# motorBoardSCH.net
KiCad netlist of a schematic drawn in Altium Designer
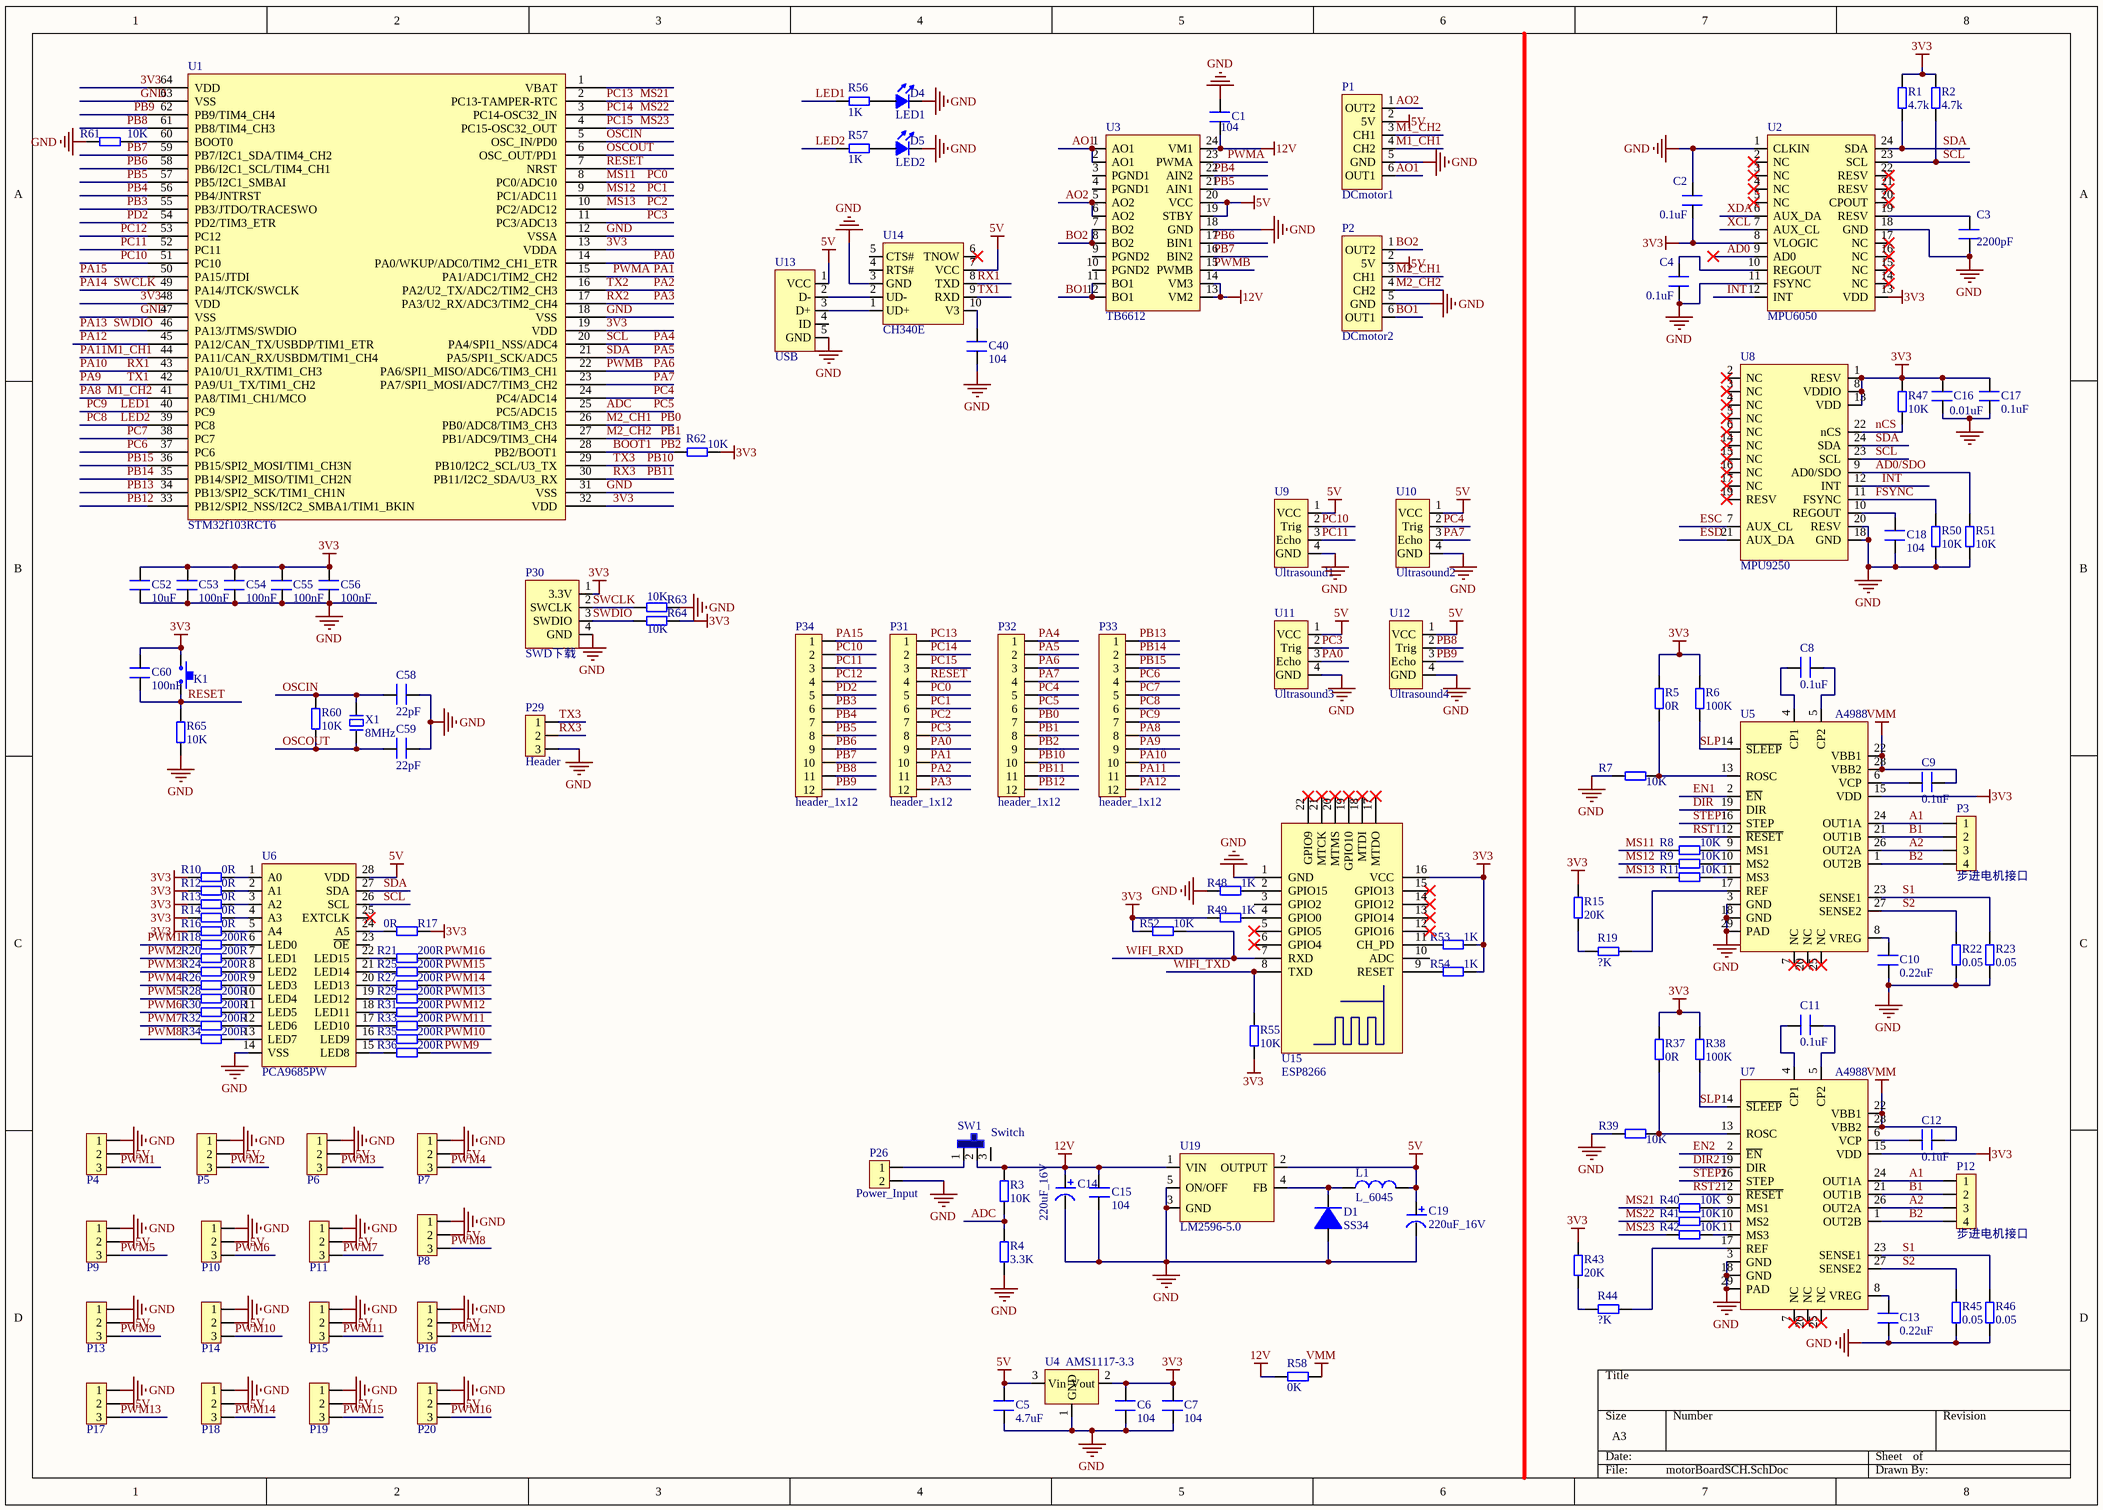
[diagram p0: motorBoardSCH.SchDoc]

(export (version "E")
  (design (tool "Eeschema 10.0.6"))
  (components
    (comp (ref "C1") (value "104") (footprint "C 0603") (libsource (lib "RobotDriverSCHLib") (part "C_0603")))
    (comp (ref "C2")
      (value "0.1uF")
      (footprint "C 0603")
      (libsource (lib "RobotDriverSCHLib") (part "C_0603"))
    )
    (comp (ref "C3")
      (value "2200pF")
      (footprint "C 0603")
      (libsource (lib "RobotDriverSCHLib") (part "C_0603"))
    )
    (comp (ref "C4")
      (value "0.1uF")
      (footprint "C 0603")
      (libsource (lib "RobotDriverSCHLib") (part "C_0603"))
    )
    (comp (ref "C5")
      (value "4.7uF")
      (footprint "C 0603")
      (libsource (lib "RobotDriverSCHLib") (part "C_0603"))
    )
    (comp (ref "C6") (value "104") (footprint "C 0603") (libsource (lib "RobotDriverSCHLib") (part "C_0603")))
    (comp (ref "C7") (value "104") (footprint "C 0603") (libsource (lib "RobotDriverSCHLib") (part "C_0603")))
    (comp (ref "C8")
      (value "0.1uF")
      (footprint "C 0603")
      (libsource (lib "RobotDriverSCHLib") (part "C_0603"))
    )
    (comp (ref "C9")
      (value "0.1uF")
      (footprint "C 0603")
      (libsource (lib "RobotDriverSCHLib") (part "C_0603"))
    )
    (comp (ref "C10")
      (value "0.22uF")
      (footprint "C 0603")
      (libsource (lib "RobotDriverSCHLib") (part "C_0603"))
    )
    (comp (ref "C11")
      (value "0.1uF")
      (footprint "C 0603")
      (libsource (lib "RobotDriverSCHLib") (part "C_0603"))
    )
    (comp (ref "C12")
      (value "0.1uF")
      (footprint "C 0603")
      (libsource (lib "RobotDriverSCHLib") (part "C_0603"))
    )
    (comp (ref "C13")
      (value "0.22uF")
      (footprint "C 0603")
      (libsource (lib "RobotDriverSCHLib") (part "C_0603"))
    )
    (comp (ref "C14")
      (value "220uF_16V")
      (footprint "CM D(6.3*7.7)")
      (libsource (lib "RobotDriverSCHLib") (part "CAP_220uF_16V"))
    )
    (comp (ref "C15")
      (value "104")
      (footprint "C 0603")
      (libsource (lib "RobotDriverSCHLib") (part "C_0603"))
    )
    (comp (ref "C16")
      (value "0.01uF")
      (footprint "C 0603")
      (libsource (lib "RobotDriverSCHLib") (part "C_0603"))
    )
    (comp (ref "C17")
      (value "0.1uF")
      (footprint "C 0603")
      (libsource (lib "RobotDriverSCHLib") (part "C_0603"))
    )
    (comp (ref "C18")
      (value "104")
      (footprint "C 0603")
      (libsource (lib "RobotDriverSCHLib") (part "C_0603"))
    )
    (comp (ref "C19")
      (value "220uF_16V")
      (footprint "CM D(6.3*7.7)")
      (libsource (lib "RobotDriverSCHLib") (part "CAP_220uF_16V"))
    )
    (comp (ref "C40")
      (value "104")
      (footprint "C 0603")
      (libsource (lib "RobotDriverSCHLib") (part "C_0603"))
    )
    (comp (ref "C52")
      (value "10uF")
      (footprint "C 0603")
      (libsource (lib "RobotDriverSCHLib") (part "C_0603"))
    )
    (comp (ref "C53")
      (value "100nF")
      (footprint "C 0603")
      (libsource (lib "RobotDriverSCHLib") (part "C_0603"))
    )
    (comp (ref "C54")
      (value "100nF")
      (footprint "C 0603")
      (libsource (lib "RobotDriverSCHLib") (part "C_0603"))
    )
    (comp (ref "C55")
      (value "100nF")
      (footprint "C 0603")
      (libsource (lib "RobotDriverSCHLib") (part "C_0603"))
    )
    (comp (ref "C56")
      (value "100nF")
      (footprint "C 0603")
      (libsource (lib "RobotDriverSCHLib") (part "C_0603"))
    )
    (comp (ref "C58")
      (value "22pF")
      (footprint "C 0603")
      (libsource (lib "RobotDriverSCHLib") (part "C_0603"))
    )
    (comp (ref "C59")
      (value "22pF")
      (footprint "C 0603")
      (libsource (lib "RobotDriverSCHLib") (part "C_0603"))
    )
    (comp (ref "C60")
      (value "100nF")
      (footprint "C 0603")
      (libsource (lib "RobotDriverSCHLib") (part "C_0603"))
    )
    (comp (ref "D1") (value "SS34") (footprint "SMA") (libsource (lib "RobotDriverSCHLib") (part "SS34")))
    (comp (ref "D4")
      (value "LED1")
      (footprint "LED 0603R")
      (libsource (lib "RobotDriverSCHLib") (part "LED"))
    )
    (comp (ref "D5")
      (value "LED2")
      (footprint "LED 0603R")
      (libsource (lib "RobotDriverSCHLib") (part "LED"))
    )
    (comp (ref "K1")
      (value "key")
      (footprint "TSW SMD-3*6*4.3")
      (libsource (lib "RobotDriverSCHLib") (part "key"))
    )
    (comp (ref "L1")
      (value "L_6045")
      (footprint "NR6045")
      (libsource (lib "RobotDriverSCHLib") (part "L_6045"))
    )
    (comp (ref "P1")
      (value "DCmotor1")
      (footprint "XH2.54-WI-6P")
      (libsource (lib "RobotDriverSCHLib") (part "DCMotor"))
    )
    (comp (ref "P2")
      (value "DCmotor2")
      (footprint "XH2.54-WI-6P")
      (libsource (lib "RobotDriverSCHLib") (part "DCMotor"))
    )
    (comp (ref "P3")
      (value "步进电机接口")
      (footprint "XH2.54-WI-4P")
      (libsource (lib "RobotDriverSCHLib") (part "header_1x4"))
    )
    (comp (ref "P4")
      (value "Head_1x3")
      (footprint "HDR2.54-LI-3P")
      (libsource (lib "RobotDriverSCHLib") (part "Head_1x3"))
    )
    (comp (ref "P5")
      (value "Head_1x3")
      (footprint "HDR2.54-LI-3P")
      (libsource (lib "RobotDriverSCHLib") (part "Head_1x3"))
    )
    (comp (ref "P6")
      (value "Head_1x3")
      (footprint "HDR2.54-LI-3P")
      (libsource (lib "RobotDriverSCHLib") (part "Head_1x3"))
    )
    (comp (ref "P7")
      (value "Head_1x3")
      (footprint "HDR2.54-LI-3P")
      (libsource (lib "RobotDriverSCHLib") (part "Head_1x3"))
    )
    (comp (ref "P8")
      (value "Head_1x3")
      (footprint "HDR2.54-LI-3P")
      (libsource (lib "RobotDriverSCHLib") (part "Head_1x3"))
    )
    (comp (ref "P9")
      (value "Head_1x3")
      (footprint "HDR2.54-LI-3P")
      (libsource (lib "RobotDriverSCHLib") (part "Head_1x3"))
    )
    (comp (ref "P10")
      (value "Head_1x3")
      (footprint "HDR2.54-LI-3P")
      (libsource (lib "RobotDriverSCHLib") (part "Head_1x3"))
    )
    (comp (ref "P11")
      (value "Head_1x3")
      (footprint "HDR2.54-LI-3P")
      (libsource (lib "RobotDriverSCHLib") (part "Head_1x3"))
    )
    (comp (ref "P12")
      (value "步进电机接口")
      (footprint "XH2.54-WI-4P")
      (libsource (lib "RobotDriverSCHLib") (part "header_1x4"))
    )
    (comp (ref "P13")
      (value "Head_1x3")
      (footprint "HDR2.54-LI-3P")
      (libsource (lib "RobotDriverSCHLib") (part "Head_1x3"))
    )
    (comp (ref "P14")
      (value "Head_1x3")
      (footprint "HDR2.54-LI-3P")
      (libsource (lib "RobotDriverSCHLib") (part "Head_1x3"))
    )
    (comp (ref "P15")
      (value "Head_1x3")
      (footprint "HDR2.54-LI-3P")
      (libsource (lib "RobotDriverSCHLib") (part "Head_1x3"))
    )
    (comp (ref "P16")
      (value "Head_1x3")
      (footprint "HDR2.54-LI-3P")
      (libsource (lib "RobotDriverSCHLib") (part "Head_1x3"))
    )
    (comp (ref "P17")
      (value "Head_1x3")
      (footprint "HDR2.54-LI-3P")
      (libsource (lib "RobotDriverSCHLib") (part "Head_1x3"))
    )
    (comp (ref "P18")
      (value "Head_1x3")
      (footprint "HDR2.54-LI-3P")
      (libsource (lib "RobotDriverSCHLib") (part "Head_1x3"))
    )
    (comp (ref "P19")
      (value "Head_1x3")
      (footprint "HDR2.54-LI-3P")
      (libsource (lib "RobotDriverSCHLib") (part "Head_1x3"))
    )
    (comp (ref "P20")
      (value "Head_1x3")
      (footprint "HDR2.54-LI-3P")
      (libsource (lib "RobotDriverSCHLib") (part "Head_1x3"))
    )
    (comp (ref "P26")
      (value "Power_Input")
      (footprint "XH2.54-WI-2P")
      (libsource (lib "RobotDriverSCHLib") (part "header_1x2"))
    )
    (comp (ref "P29")
      (value "Header")
      (footprint "HDR2.54-LI-3P")
      (libsource (lib "RobotDriverSCHLib") (part "header_1x3"))
    )
    (comp (ref "P30")
      (value "SWD下载")
      (footprint "HDR2.54-WI-4P")
      (libsource (lib "RobotDriverSCHLib") (part "SWD"))
    )
    (comp (ref "P31")
      (value "header_1x12")
      (footprint "HDR2.54-LI-12P")
      (libsource (lib "RobotDriverSCHLib") (part "header_1x12"))
    )
    (comp (ref "P32")
      (value "header_1x12")
      (footprint "HDR2.54-LI-12P")
      (libsource (lib "RobotDriverSCHLib") (part "header_1x12"))
    )
    (comp (ref "P33")
      (value "header_1x12")
      (footprint "HDR2.54-LI-12P")
      (libsource (lib "RobotDriverSCHLib") (part "header_1x12"))
    )
    (comp (ref "P34")
      (value "header_1x12")
      (footprint "HDR2.54-LI-12P")
      (libsource (lib "RobotDriverSCHLib") (part "header_1x12"))
    )
    (comp (ref "R1") (value "4.7k") (footprint "0603R") (libsource (lib "RobotDriverSCHLib") (part "R_0603")))
    (comp (ref "R2") (value "4.7k") (footprint "0603R") (libsource (lib "RobotDriverSCHLib") (part "R_0603")))
    (comp (ref "R3") (value "10K") (footprint "0603R") (libsource (lib "RobotDriverSCHLib") (part "R_0603")))
    (comp (ref "R4") (value "3.3K") (footprint "0603R") (libsource (lib "RobotDriverSCHLib") (part "R_0603")))
    (comp (ref "R5") (value "0R") (footprint "0603R") (libsource (lib "RobotDriverSCHLib") (part "R_0603")))
    (comp (ref "R6") (value "100K") (footprint "0603R") (libsource (lib "RobotDriverSCHLib") (part "R_0603")))
    (comp (ref "R7") (value "10K") (footprint "0603R") (libsource (lib "RobotDriverSCHLib") (part "R_0603")))
    (comp (ref "R8") (value "10K") (footprint "0603R") (libsource (lib "RobotDriverSCHLib") (part "R_0603")))
    (comp (ref "R9") (value "10K") (footprint "0603R") (libsource (lib "RobotDriverSCHLib") (part "R_0603")))
    (comp (ref "R10") (value "0R") (footprint "0603R") (libsource (lib "RobotDriverSCHLib") (part "R_0603")))
    (comp (ref "R11") (value "10K") (footprint "0603R") (libsource (lib "RobotDriverSCHLib") (part "R_0603")))
    (comp (ref "R12") (value "0R") (footprint "0603R") (libsource (lib "RobotDriverSCHLib") (part "R_0603")))
    (comp (ref "R13") (value "0R") (footprint "0603R") (libsource (lib "RobotDriverSCHLib") (part "R_0603")))
    (comp (ref "R14") (value "0R") (footprint "0603R") (libsource (lib "RobotDriverSCHLib") (part "R_0603")))
    (comp (ref "R15") (value "20K") (footprint "0603R") (libsource (lib "RobotDriverSCHLib") (part "R_0603")))
    (comp (ref "R16") (value "0R") (footprint "0603R") (libsource (lib "RobotDriverSCHLib") (part "R_0603")))
    (comp (ref "R17") (value "0R") (footprint "0603R") (libsource (lib "RobotDriverSCHLib") (part "R_0603")))
    (comp (ref "R18")
      (value "200R")
      (footprint "0603R")
      (libsource (lib "RobotDriverSCHLib") (part "R_0603"))
    )
    (comp (ref "R19") (value "?K") (footprint "0603R") (libsource (lib "RobotDriverSCHLib") (part "R_0603")))
    (comp (ref "R20")
      (value "200R")
      (footprint "0603R")
      (libsource (lib "RobotDriverSCHLib") (part "R_0603"))
    )
    (comp (ref "R21")
      (value "200R")
      (footprint "0603R")
      (libsource (lib "RobotDriverSCHLib") (part "R_0603"))
    )
    (comp (ref "R22")
      (value "0.05")
      (footprint "0603R")
      (libsource (lib "RobotDriverSCHLib") (part "R_0603"))
    )
    (comp (ref "R23")
      (value "0.05")
      (footprint "0603R")
      (libsource (lib "RobotDriverSCHLib") (part "R_0603"))
    )
    (comp (ref "R24")
      (value "200R")
      (footprint "0603R")
      (libsource (lib "RobotDriverSCHLib") (part "R_0603"))
    )
    (comp (ref "R25")
      (value "200R")
      (footprint "0603R")
      (libsource (lib "RobotDriverSCHLib") (part "R_0603"))
    )
    (comp (ref "R26")
      (value "200R")
      (footprint "0603R")
      (libsource (lib "RobotDriverSCHLib") (part "R_0603"))
    )
    (comp (ref "R27")
      (value "200R")
      (footprint "0603R")
      (libsource (lib "RobotDriverSCHLib") (part "R_0603"))
    )
    (comp (ref "R28")
      (value "200R")
      (footprint "0603R")
      (libsource (lib "RobotDriverSCHLib") (part "R_0603"))
    )
    (comp (ref "R29")
      (value "200R")
      (footprint "0603R")
      (libsource (lib "RobotDriverSCHLib") (part "R_0603"))
    )
    (comp (ref "R30")
      (value "200R")
      (footprint "0603R")
      (libsource (lib "RobotDriverSCHLib") (part "R_0603"))
    )
    (comp (ref "R31")
      (value "200R")
      (footprint "0603R")
      (libsource (lib "RobotDriverSCHLib") (part "R_0603"))
    )
    (comp (ref "R32")
      (value "200R")
      (footprint "0603R")
      (libsource (lib "RobotDriverSCHLib") (part "R_0603"))
    )
    (comp (ref "R33")
      (value "200R")
      (footprint "0603R")
      (libsource (lib "RobotDriverSCHLib") (part "R_0603"))
    )
    (comp (ref "R34")
      (value "200R")
      (footprint "0603R")
      (libsource (lib "RobotDriverSCHLib") (part "R_0603"))
    )
    (comp (ref "R35")
      (value "200R")
      (footprint "0603R")
      (libsource (lib "RobotDriverSCHLib") (part "R_0603"))
    )
    (comp (ref "R36")
      (value "200R")
      (footprint "0603R")
      (libsource (lib "RobotDriverSCHLib") (part "R_0603"))
    )
    (comp (ref "R37") (value "0R") (footprint "0603R") (libsource (lib "RobotDriverSCHLib") (part "R_0603")))
    (comp (ref "R38")
      (value "100K")
      (footprint "0603R")
      (libsource (lib "RobotDriverSCHLib") (part "R_0603"))
    )
    (comp (ref "R39") (value "10K") (footprint "0603R") (libsource (lib "RobotDriverSCHLib") (part "R_0603")))
    (comp (ref "R40") (value "10K") (footprint "0603R") (libsource (lib "RobotDriverSCHLib") (part "R_0603")))
    (comp (ref "R41") (value "10K") (footprint "0603R") (libsource (lib "RobotDriverSCHLib") (part "R_0603")))
    (comp (ref "R42") (value "10K") (footprint "0603R") (libsource (lib "RobotDriverSCHLib") (part "R_0603")))
    (comp (ref "R43") (value "20K") (footprint "0603R") (libsource (lib "RobotDriverSCHLib") (part "R_0603")))
    (comp (ref "R44") (value "?K") (footprint "0603R") (libsource (lib "RobotDriverSCHLib") (part "R_0603")))
    (comp (ref "R45")
      (value "0.05")
      (footprint "0603R")
      (libsource (lib "RobotDriverSCHLib") (part "R_0603"))
    )
    (comp (ref "R46")
      (value "0.05")
      (footprint "0603R")
      (libsource (lib "RobotDriverSCHLib") (part "R_0603"))
    )
    (comp (ref "R47") (value "10K") (footprint "0603R") (libsource (lib "RobotDriverSCHLib") (part "R_0603")))
    (comp (ref "R48") (value "1K") (footprint "0603R") (libsource (lib "RobotDriverSCHLib") (part "R_0603")))
    (comp (ref "R49") (value "1K") (footprint "0603R") (libsource (lib "RobotDriverSCHLib") (part "R_0603")))
    (comp (ref "R50") (value "10K") (footprint "0603R") (libsource (lib "RobotDriverSCHLib") (part "R_0603")))
    (comp (ref "R51") (value "10K") (footprint "0603R") (libsource (lib "RobotDriverSCHLib") (part "R_0603")))
    (comp (ref "R52") (value "10K") (footprint "0603R") (libsource (lib "RobotDriverSCHLib") (part "R_0603")))
    (comp (ref "R53") (value "1K") (footprint "0603R") (libsource (lib "RobotDriverSCHLib") (part "R_0603")))
    (comp (ref "R54") (value "1K") (footprint "0603R") (libsource (lib "RobotDriverSCHLib") (part "R_0603")))
    (comp (ref "R55") (value "10K") (footprint "0603R") (libsource (lib "RobotDriverSCHLib") (part "R_0603")))
    (comp (ref "R56") (value "1K") (footprint "0603R") (libsource (lib "RobotDriverSCHLib") (part "R_0603")))
    (comp (ref "R57") (value "1K") (footprint "0603R") (libsource (lib "RobotDriverSCHLib") (part "R_0603")))
    (comp (ref "R58") (value "0K") (footprint "0603R") (libsource (lib "RobotDriverSCHLib") (part "R_0603")))
    (comp (ref "R60") (value "10K") (footprint "0603R") (libsource (lib "RobotDriverSCHLib") (part "R_0603")))
    (comp (ref "R61") (value "10K") (footprint "0603R") (libsource (lib "RobotDriverSCHLib") (part "R_0603")))
    (comp (ref "R62") (value "10K") (footprint "0603R") (libsource (lib "RobotDriverSCHLib") (part "R_0603")))
    (comp (ref "R63") (value "10K") (footprint "0603R") (libsource (lib "RobotDriverSCHLib") (part "R_0603")))
    (comp (ref "R64") (value "10K") (footprint "0603R") (libsource (lib "RobotDriverSCHLib") (part "R_0603")))
    (comp (ref "R65") (value "10K") (footprint "0603R") (libsource (lib "RobotDriverSCHLib") (part "R_0603")))
    (comp (ref "SW1")
      (value "Switch")
      (footprint "SS12D10")
      (libsource (lib "RobotDriverSCHLib") (part "SS12D10"))
    )
    (comp (ref "U1")
      (value "STM32f103RCT6")
      (footprint "LQFP_64")
      (libsource (lib "RobotDriverSCHLib") (part "STM32f103RCT6"))
    )
    (comp (ref "U2")
      (value "MPU6050")
      (footprint "QFN24 4x4")
      (libsource (lib "RobotDriverSCHLib") (part "MPU6050"))
    )
    (comp (ref "U3")
      (value "TB6612")
      (footprint "SSOP24")
      (libsource (lib "RobotDriverSCHLib") (part "TB6612FNG"))
    )
    (comp (ref "U4")
      (value "AMS1117-3.3")
      (footprint "SOT-223")
      (libsource (lib "RobotDriverSCHLib") (part "AMS1117-3.3"))
    )
    (comp (ref "U5")
      (value "A4988")
      (footprint "QFN28 5x5")
      (libsource (lib "RobotDriverSCHLib") (part "A4988"))
    )
    (comp (ref "U6")
      (value "PCA9685PW")
      (footprint "TSSOP28")
      (libsource (lib "RobotDriverSCHLib") (part "PCA9685PW"))
    )
    (comp (ref "U7")
      (value "A4988")
      (footprint "QFN28 5x5")
      (libsource (lib "RobotDriverSCHLib") (part "A4988"))
    )
    (comp (ref "U8")
      (value "MPU9250")
      (footprint "QFN24_3x3")
      (libsource (lib "RobotDriverSCHLib") (part "MPU9250"))
    )
    (comp (ref "U9")
      (value "Ultrasound1")
      (footprint "超声波模块")
      (libsource (lib "RobotDriverSCHLib") (part "Ultrasound"))
    )
    (comp (ref "U10")
      (value "Ultrasound2")
      (footprint "超声波模块")
      (libsource (lib "RobotDriverSCHLib") (part "Ultrasound"))
    )
    (comp (ref "U11")
      (value "Ultrasound3")
      (footprint "超声波模块")
      (libsource (lib "RobotDriverSCHLib") (part "Ultrasound"))
    )
    (comp (ref "U12")
      (value "Ultrasound4")
      (footprint "超声波模块")
      (libsource (lib "RobotDriverSCHLib") (part "Ultrasound"))
    )
    (comp (ref "U13") (value "USB") (footprint "USB-MICRO_D") (libsource (lib "pin_pi") (part "MicroUSB_D")))
    (comp (ref "U14") (value "CH340E") (footprint "CH340E") (libsource (lib "pin_pi") (part "CH340E")))
    (comp (ref "U15")
      (value "ESP8266")
      (footprint "ESP8266")
      (libsource (lib "RobotDriverSCHLib") (part "ESP8266"))
    )
    (comp (ref "U19")
      (value "LM2596-5.0")
      (footprint "TO263-5A")
      (libsource (lib "RobotDriverSCHLib") (part "LM2596-5.0"))
    )
    (comp (ref "X1")
      (value "8MHz")
      (footprint "OSC HC-49SMD")
      (libsource (lib "RobotDriverSCHLib") (part "XTAL_8MHz"))
    )
  )
  (nets
    (net (code "1") (name "/A1") (class "Default")
      (node (ref "P12") (pin "1") (pinfunction "1_1") (pintype "passive"))
      (node (ref "P3") (pin "1") (pinfunction "1_1") (pintype "passive"))
      (node (ref "U5") (pin "24") (pinfunction "OUT1A_24") (pintype "passive"))
      (node (ref "U7") (pin "24") (pinfunction "OUT1A_24") (pintype "passive"))
    )
    (net (code "2") (name "/A2") (class "Default")
      (node (ref "P12") (pin "3") (pinfunction "3_3") (pintype "passive"))
      (node (ref "P3") (pin "3") (pinfunction "3_3") (pintype "passive"))
      (node (ref "U5") (pin "26") (pinfunction "OUT2A_26") (pintype "passive"))
      (node (ref "U7") (pin "26") (pinfunction "OUT2A_26") (pintype "passive"))
    )
    (net (code "3") (name "/AD0") (class "Default")
      (node (ref "U2") (pin "9") (pinfunction "AD0_9") (pintype "passive+no_connect"))
    )
    (net (code "4") (name "/AD0{slash}SDO") (class "Default")
      (node (ref "R51") (pin "2") (pinfunction "2_2") (pintype "passive"))
      (node (ref "U8") (pin "9") (pinfunction "AD0/SDO_9") (pintype "passive"))
    )
    (net (code "5") (name "/ADC") (class "Default")
      (node (ref "P32") (pin "6") (pinfunction "6_6") (pintype "passive"))
      (node (ref "R3") (pin "1") (pinfunction "1_1") (pintype "passive"))
      (node (ref "R4") (pin "2") (pinfunction "2_2") (pintype "passive"))
      (node (ref "U1") (pin "25") (pinfunction "PC5/ADC15_25") (pintype "passive"))
    )
    (net (code "6") (name "/AO1") (class "Default")
      (node (ref "P1") (pin "6") (pinfunction "OUT1_6") (pintype "passive"))
      (node (ref "U3") (pin "1") (pinfunction "AO1_1") (pintype "passive"))
      (node (ref "U3") (pin "2") (pinfunction "AO1_2") (pintype "passive"))
    )
    (net (code "7") (name "/AO2") (class "Default")
      (node (ref "P1") (pin "1") (pinfunction "OUT2_1") (pintype "passive"))
      (node (ref "U3") (pin "5") (pinfunction "AO2_5") (pintype "passive"))
      (node (ref "U3") (pin "6") (pinfunction "AO2_6") (pintype "passive"))
    )
    (net (code "8") (name "/B1") (class "Default")
      (node (ref "P12") (pin "2") (pinfunction "2_2") (pintype "passive"))
      (node (ref "P3") (pin "2") (pinfunction "2_2") (pintype "passive"))
      (node (ref "U5") (pin "21") (pinfunction "OUT1B_21") (pintype "passive"))
      (node (ref "U7") (pin "21") (pinfunction "OUT1B_21") (pintype "passive"))
    )
    (net (code "9") (name "/B2") (class "Default")
      (node (ref "P12") (pin "4") (pinfunction "4_4") (pintype "passive"))
      (node (ref "P3") (pin "4") (pinfunction "4_4") (pintype "passive"))
      (node (ref "U5") (pin "1") (pinfunction "OUT2B_1") (pintype "passive"))
      (node (ref "U7") (pin "1") (pinfunction "OUT2B_1") (pintype "passive"))
    )
    (net (code "10") (name "/BO1") (class "Default")
      (node (ref "P2") (pin "6") (pinfunction "OUT1_6") (pintype "passive"))
      (node (ref "U3") (pin "11") (pinfunction "BO1_11") (pintype "passive"))
      (node (ref "U3") (pin "12") (pinfunction "BO1_12") (pintype "passive"))
    )
    (net (code "11") (name "/BO2") (class "Default")
      (node (ref "P2") (pin "1") (pinfunction "OUT2_1") (pintype "passive"))
      (node (ref "U3") (pin "7") (pinfunction "BO2_7") (pintype "passive"))
      (node (ref "U3") (pin "8") (pinfunction "BO2_8") (pintype "passive"))
    )
    (net (code "12") (name "/BOOT1") (class "Default")
      (node (ref "P32") (pin "9") (pinfunction "9_9") (pintype "passive"))
      (node (ref "R62") (pin "2") (pinfunction "2_2") (pintype "passive"))
      (node (ref "U1") (pin "28") (pinfunction "PB2/BOOT1_28") (pintype "passive"))
    )
    (net (code "13") (name "/DIR") (class "Default")
      (node (ref "U5") (pin "19") (pinfunction "DIR_19") (pintype "passive"))
    )
    (net (code "14") (name "/DIR2") (class "Default")
      (node (ref "U7") (pin "19") (pinfunction "DIR_19") (pintype "passive"))
    )
    (net (code "15") (name "/EN1") (class "Default")
      (node (ref "U5") (pin "2") (pinfunction "~{EN}_2") (pintype "passive"))
    )
    (net (code "16") (name "/EN2") (class "Default")
      (node (ref "U7") (pin "2") (pinfunction "~{EN}_2") (pintype "passive"))
    )
    (net (code "17") (name "/ESC") (class "Default")
      (node (ref "U8") (pin "7") (pinfunction "AUX_CL_7") (pintype "passive"))
    )
    (net (code "18") (name "/ESD") (class "Default")
      (node (ref "U8") (pin "21") (pinfunction "AUX_DA_21") (pintype "passive"))
    )
    (net (code "19") (name "/FSYNC") (class "Default")
      (node (ref "R50") (pin "2") (pinfunction "2_2") (pintype "passive"))
      (node (ref "U8") (pin "11") (pinfunction "FSYNC_11") (pintype "passive"))
    )
    (net (code "20") (name "/INT") (class "Default")
      (node (ref "U2") (pin "12") (pinfunction "INT_12") (pintype "passive"))
      (node (ref "U8") (pin "12") (pinfunction "INT_12") (pintype "passive"))
    )
    (net (code "21") (name "/LED1") (class "Default")
      (node (ref "P33") (pin "7") (pinfunction "7_7") (pintype "passive"))
      (node (ref "R56") (pin "1") (pinfunction "1_1") (pintype "passive"))
      (node (ref "U1") (pin "40") (pinfunction "PC9_40") (pintype "passive"))
    )
    (net (code "22") (name "/LED2") (class "Default")
      (node (ref "P33") (pin "6") (pinfunction "6_6") (pintype "passive"))
      (node (ref "R57") (pin "1") (pinfunction "1_1") (pintype "passive"))
      (node (ref "U1") (pin "39") (pinfunction "PC8_39") (pintype "passive"))
    )
    (net (code "23") (name "/M1_CH1") (class "Default")
      (node (ref "P1") (pin "4") (pinfunction "CH2_4") (pintype "passive"))
      (node (ref "P33") (pin "11") (pinfunction "11_11") (pintype "passive"))
      (node (ref "U1") (pin "44") (pinfunction "PA11/CAN_RX/USBDM/TIM1_CH4_44") (pintype "passive"))
    )
    (net (code "24") (name "/M1_CH2") (class "Default")
      (node (ref "P1") (pin "3") (pinfunction "CH1_3") (pintype "passive"))
      (node (ref "P33") (pin "8") (pinfunction "8_8") (pintype "passive"))
      (node (ref "U1") (pin "41") (pinfunction "PA8/TIM1_CH1/MCO_41") (pintype "passive"))
    )
    (net (code "25") (name "/M2_CH1") (class "Default")
      (node (ref "P2") (pin "3") (pinfunction "CH1_3") (pintype "passive"))
      (node (ref "P32") (pin "7") (pinfunction "7_7") (pintype "passive"))
      (node (ref "U1") (pin "26") (pinfunction "PB0/ADC8/TIM3_CH3_26") (pintype "passive"))
    )
    (net (code "26") (name "/M2_CH2") (class "Default")
      (node (ref "P2") (pin "4") (pinfunction "CH2_4") (pintype "passive"))
      (node (ref "P32") (pin "8") (pinfunction "8_8") (pintype "passive"))
      (node (ref "U1") (pin "27") (pinfunction "PB1/ADC9/TIM3_CH4_27") (pintype "passive"))
    )
    (net (code "27") (name "/MS11") (class "Default")
      (node (ref "P31") (pin "5") (pinfunction "5_5") (pintype "passive"))
      (node (ref "R8") (pin "2") (pinfunction "2_2") (pintype "passive"))
      (node (ref "U1") (pin "8") (pinfunction "PC0/ADC10_8") (pintype "passive"))
    )
    (net (code "28") (name "/MS12") (class "Default")
      (node (ref "P31") (pin "6") (pinfunction "6_6") (pintype "passive"))
      (node (ref "R9") (pin "2") (pinfunction "2_2") (pintype "passive"))
      (node (ref "U1") (pin "9") (pinfunction "PC1/ADC11_9") (pintype "passive"))
    )
    (net (code "29") (name "/MS13") (class "Default")
      (node (ref "P31") (pin "7") (pinfunction "7_7") (pintype "passive"))
      (node (ref "R11") (pin "2") (pinfunction "2_2") (pintype "passive"))
      (node (ref "U1") (pin "10") (pinfunction "PC2/ADC12_10") (pintype "passive"))
    )
    (net (code "30") (name "/MS21") (class "Default")
      (node (ref "P31") (pin "1") (pinfunction "1_1") (pintype "passive"))
      (node (ref "R40") (pin "2") (pinfunction "2_2") (pintype "passive"))
      (node (ref "U1") (pin "2") (pinfunction "PC13-TAMPER-RTC_2") (pintype "passive"))
    )
    (net (code "31") (name "/MS22") (class "Default")
      (node (ref "P31") (pin "2") (pinfunction "2_2") (pintype "passive"))
      (node (ref "R41") (pin "2") (pinfunction "2_2") (pintype "passive"))
      (node (ref "U1") (pin "3") (pinfunction "PC14-OSC32_IN_3") (pintype "passive"))
    )
    (net (code "32") (name "/MS23") (class "Default")
      (node (ref "P31") (pin "3") (pinfunction "3_3") (pintype "passive"))
      (node (ref "R42") (pin "2") (pinfunction "2_2") (pintype "passive"))
      (node (ref "U1") (pin "4") (pinfunction "PC15-OSC32_OUT_4") (pintype "passive"))
    )
    (net (code "33") (name "/OSCIN") (class "Default")
      (node (ref "C58") (pin "2") (pinfunction "2_2") (pintype "passive"))
      (node (ref "R60") (pin "2") (pinfunction "2_2") (pintype "passive"))
      (node (ref "U1") (pin "5") (pinfunction "OSC_IN/PD0_5") (pintype "passive"))
      (node (ref "X1") (pin "2") (pinfunction "2_2") (pintype "passive"))
    )
    (net (code "34") (name "/OSCOUT") (class "Default")
      (node (ref "C59") (pin "2") (pinfunction "2_2") (pintype "passive"))
      (node (ref "R60") (pin "1") (pinfunction "1_1") (pintype "passive"))
      (node (ref "U1") (pin "6") (pinfunction "OSC_OUT/PD1_6") (pintype "passive"))
      (node (ref "X1") (pin "1") (pinfunction "1_1") (pintype "passive"))
    )
    (net (code "35") (name "/PA0") (class "Default")
      (node (ref "P31") (pin "9") (pinfunction "9_9") (pintype "passive"))
      (node (ref "U1") (pin "14") (pinfunction "PA0/WKUP/ADC0/TIM2_CH1_ETR_14") (pintype "passive"))
      (node (ref "U11") (pin "3") (pinfunction "Echo_3") (pintype "passive"))
    )
    (net (code "36") (name "/PA1") (class "Default")
      (node (ref "P31") (pin "10") (pinfunction "10_10") (pintype "passive"))
      (node (ref "U1") (pin "15") (pinfunction "PA1/ADC1/TIM2_CH2_15") (pintype "passive"))
      (node (ref "U3") (pin "23") (pinfunction "PWMA_23") (pintype "passive"))
    )
    (net (code "37") (name "/PA2") (class "Default")
      (node (ref "P31") (pin "11") (pinfunction "11_11") (pintype "passive"))
      (node (ref "U1") (pin "16") (pinfunction "PA2/U2_TX/ADC2/TIM2_CH3_16") (pintype "passive"))
    )
    (net (code "38") (name "/PA3") (class "Default")
      (node (ref "P31") (pin "12") (pinfunction "12_12") (pintype "passive"))
      (node (ref "U1") (pin "17") (pinfunction "PA3/U2_RX/ADC3/TIM2_CH4_17") (pintype "passive"))
    )
    (net (code "39") (name "/PA4") (class "Default")
      (node (ref "P32") (pin "1") (pinfunction "1_1") (pintype "passive"))
      (node (ref "R2") (pin "1") (pinfunction "1_1") (pintype "passive"))
      (node (ref "U1") (pin "20") (pinfunction "PA4/SPI1_NSS/ADC4_20") (pintype "passive"))
      (node (ref "U2") (pin "23") (pinfunction "SCL_23") (pintype "passive"))
      (node (ref "U6") (pin "26") (pinfunction "SCL_26") (pintype "passive"))
      (node (ref "U8") (pin "23") (pinfunction "SCL_23") (pintype "passive"))
    )
    (net (code "40") (name "/PA5") (class "Default")
      (node (ref "P32") (pin "2") (pinfunction "2_2") (pintype "passive"))
      (node (ref "R1") (pin "1") (pinfunction "1_1") (pintype "passive"))
      (node (ref "U1") (pin "21") (pinfunction "PA5/SPI1_SCK/ADC5_21") (pintype "passive"))
      (node (ref "U2") (pin "24") (pinfunction "SDA_24") (pintype "passive"))
      (node (ref "U6") (pin "27") (pinfunction "SDA_27") (pintype "passive"))
      (node (ref "U8") (pin "24") (pinfunction "SDA_24") (pintype "passive"))
    )
    (net (code "41") (name "/PA6") (class "Default")
      (node (ref "P32") (pin "3") (pinfunction "3_3") (pintype "passive"))
      (node (ref "U1") (pin "22") (pinfunction "PA6/SPI1_MISO/ADC6/TIM3_CH1_22") (pintype "passive"))
      (node (ref "U3") (pin "15") (pinfunction "PWMB_15") (pintype "passive"))
    )
    (net (code "42") (name "/PA7") (class "Default")
      (node (ref "P32") (pin "4") (pinfunction "4_4") (pintype "passive"))
      (node (ref "U1") (pin "23") (pinfunction "PA7/SPI1_MOSI/ADC7/TIM3_CH2_23") (pintype "passive"))
      (node (ref "U10") (pin "3") (pinfunction "Echo_3") (pintype "passive"))
    )
    (net (code "43") (name "/PA9") (class "Default")
      (node (ref "P33") (pin "9") (pinfunction "9_9") (pintype "passive"))
      (node (ref "U1") (pin "42") (pinfunction "PA9/U1_TX/TIM1_CH2_42") (pintype "passive"))
      (node (ref "U14") (pin "9") (pinfunction "RXD_9") (pintype "passive"))
    )
    (net (code "44") (name "/PA10") (class "Default")
      (node (ref "P33") (pin "10") (pinfunction "10_10") (pintype "passive"))
      (node (ref "U1") (pin "43") (pinfunction "PA10/U1_RX/TIM1_CH3_43") (pintype "passive"))
      (node (ref "U14") (pin "8") (pinfunction "TXD_8") (pintype "passive"))
    )
    (net (code "45") (name "/PA12") (class "Default")
      (node (ref "P33") (pin "12") (pinfunction "12_12") (pintype "passive"))
      (node (ref "U1") (pin "45") (pinfunction "PA12/CAN_TX/USBDP/TIM1_ETR_45") (pintype "passive"))
    )
    (net (code "46") (name "/PA13") (class "Default")
      (node (ref "P30") (pin "3") (pinfunction "SWDIO_3") (pintype "passive"))
      (node (ref "R64") (pin "2") (pinfunction "2_2") (pintype "passive"))
      (node (ref "U1") (pin "46") (pinfunction "PA13/JTMS/SWDIO_46") (pintype "passive"))
    )
    (net (code "47") (name "/PA14") (class "Default")
      (node (ref "P30") (pin "2") (pinfunction "SWCLK_2") (pintype "passive"))
      (node (ref "R63") (pin "2") (pinfunction "2_2") (pintype "passive"))
      (node (ref "U1") (pin "49") (pinfunction "PA14/JTCK/SWCLK_49") (pintype "passive"))
    )
    (net (code "48") (name "/PA15") (class "Default")
      (node (ref "P34") (pin "1") (pinfunction "1_1") (pintype "passive"))
      (node (ref "U1") (pin "50") (pinfunction "PA15/JTDI_50") (pintype "passive"))
    )
    (net (code "49") (name "/PB3") (class "Default")
      (node (ref "P34") (pin "6") (pinfunction "6_6") (pintype "passive"))
      (node (ref "U1") (pin "55") (pinfunction "PB3/JTDO/TRACESWO_55") (pintype "passive"))
    )
    (net (code "50") (name "/PB4") (class "Default")
      (node (ref "P34") (pin "7") (pinfunction "7_7") (pintype "passive"))
      (node (ref "U1") (pin "56") (pinfunction "PB4/JNTRST_56") (pintype "passive"))
      (node (ref "U3") (pin "22") (pinfunction "AIN2_22") (pintype "passive"))
    )
    (net (code "51") (name "/PB5") (class "Default")
      (node (ref "P34") (pin "8") (pinfunction "8_8") (pintype "passive"))
      (node (ref "U1") (pin "57") (pinfunction "PB5/I2C1_SMBAI_57") (pintype "passive"))
      (node (ref "U3") (pin "21") (pinfunction "AIN1_21") (pintype "passive"))
    )
    (net (code "52") (name "/PB6") (class "Default")
      (node (ref "P34") (pin "9") (pinfunction "9_9") (pintype "passive"))
      (node (ref "U1") (pin "58") (pinfunction "PB6/I2C1_SCL/TIM4_CH1_58") (pintype "passive"))
      (node (ref "U3") (pin "17") (pinfunction "BIN1_17") (pintype "passive"))
    )
    (net (code "53") (name "/PB7") (class "Default")
      (node (ref "P34") (pin "10") (pinfunction "10_10") (pintype "passive"))
      (node (ref "U1") (pin "59") (pinfunction "PB7/I2C1_SDA/TIM4_CH2_59") (pintype "passive"))
      (node (ref "U3") (pin "16") (pinfunction "BIN2_16") (pintype "passive"))
    )
    (net (code "54") (name "/PB8") (class "Default")
      (node (ref "P34") (pin "11") (pinfunction "11_11") (pintype "passive"))
      (node (ref "U1") (pin "61") (pinfunction "PB8/TIM4_CH3_61") (pintype "passive"))
      (node (ref "U12") (pin "2") (pinfunction "Trig_2") (pintype "passive"))
    )
    (net (code "55") (name "/PB9") (class "Default")
      (node (ref "P34") (pin "12") (pinfunction "12_12") (pintype "passive"))
      (node (ref "U1") (pin "62") (pinfunction "PB9/TIM4_CH4_62") (pintype "passive"))
      (node (ref "U12") (pin "3") (pinfunction "Echo_3") (pintype "passive"))
    )
    (net (code "56") (name "/PB10") (class "Default")
      (node (ref "P29") (pin "1") (pinfunction "1_1") (pintype "passive"))
      (node (ref "P32") (pin "10") (pinfunction "10_10") (pintype "passive"))
      (node (ref "U1") (pin "29") (pinfunction "PB10/I2C2_SCL/U3_TX_29") (pintype "passive"))
    )
    (net (code "57") (name "/PB11") (class "Default")
      (node (ref "P29") (pin "2") (pinfunction "2_2") (pintype "passive"))
      (node (ref "P32") (pin "11") (pinfunction "11_11") (pintype "passive"))
      (node (ref "U1") (pin "30") (pinfunction "PB11/I2C2_SDA/U3_RX_30") (pintype "passive"))
    )
    (net (code "58") (name "/PB12") (class "Default")
      (node (ref "P32") (pin "12") (pinfunction "12_12") (pintype "passive"))
      (node (ref "U1") (pin "33") (pinfunction "PB12/SPI2_NSS/I2C2_SMBA1/TIM1_BKIN_33") (pintype "passive"))
    )
    (net (code "59") (name "/PB13") (class "Default")
      (node (ref "P33") (pin "1") (pinfunction "1_1") (pintype "passive"))
      (node (ref "U1") (pin "34") (pinfunction "PB13/SPI2_SCK/TIM1_CH1N_34") (pintype "passive"))
    )
    (net (code "60") (name "/PB14") (class "Default")
      (node (ref "P33") (pin "2") (pinfunction "2_2") (pintype "passive"))
      (node (ref "U1") (pin "35") (pinfunction "PB14/SPI2_MISO/TIM1_CH2N_35") (pintype "passive"))
    )
    (net (code "61") (name "/PB15") (class "Default")
      (node (ref "P33") (pin "3") (pinfunction "3_3") (pintype "passive"))
      (node (ref "U1") (pin "36") (pinfunction "PB15/SPI2_MOSI/TIM1_CH3N_36") (pintype "passive"))
    )
    (net (code "62") (name "/PC3") (class "Default")
      (node (ref "P31") (pin "8") (pinfunction "8_8") (pintype "passive"))
      (node (ref "U1") (pin "11") (pinfunction "PC3/ADC13_11") (pintype "passive"))
      (node (ref "U11") (pin "2") (pinfunction "Trig_2") (pintype "passive"))
    )
    (net (code "63") (name "/PC4") (class "Default")
      (node (ref "P32") (pin "5") (pinfunction "5_5") (pintype "passive"))
      (node (ref "U1") (pin "24") (pinfunction "PC4/ADC14_24") (pintype "passive"))
      (node (ref "U10") (pin "2") (pinfunction "Trig_2") (pintype "passive"))
    )
    (net (code "64") (name "/PC6") (class "Default")
      (node (ref "P33") (pin "4") (pinfunction "4_4") (pintype "passive"))
      (node (ref "U1") (pin "37") (pinfunction "PC6_37") (pintype "passive"))
    )
    (net (code "65") (name "/PC7") (class "Default")
      (node (ref "P33") (pin "5") (pinfunction "5_5") (pintype "passive"))
      (node (ref "U1") (pin "38") (pinfunction "PC7_38") (pintype "passive"))
    )
    (net (code "66") (name "/PC10") (class "Default")
      (node (ref "P34") (pin "2") (pinfunction "2_2") (pintype "passive"))
      (node (ref "U1") (pin "51") (pinfunction "PC10_51") (pintype "passive"))
      (node (ref "U9") (pin "2") (pinfunction "Trig_2") (pintype "passive"))
    )
    (net (code "67") (name "/PC11") (class "Default")
      (node (ref "P34") (pin "3") (pinfunction "3_3") (pintype "passive"))
      (node (ref "U1") (pin "52") (pinfunction "PC11_52") (pintype "passive"))
      (node (ref "U9") (pin "3") (pinfunction "Echo_3") (pintype "passive"))
    )
    (net (code "68") (name "/PC12") (class "Default")
      (node (ref "P34") (pin "4") (pinfunction "4_4") (pintype "passive"))
      (node (ref "U1") (pin "53") (pinfunction "PC12_53") (pintype "passive"))
    )
    (net (code "69") (name "/PD2") (class "Default")
      (node (ref "P34") (pin "5") (pinfunction "5_5") (pintype "passive"))
      (node (ref "U1") (pin "54") (pinfunction "PD2/TIM3_ETR_54") (pintype "passive"))
    )
    (net (code "70") (name "/PWM1") (class "Default")
      (node (ref "P4") (pin "3") (pinfunction "3_3") (pintype "passive"))
      (node (ref "R18") (pin "1") (pinfunction "1_1") (pintype "passive"))
    )
    (net (code "71") (name "/PWM2") (class "Default")
      (node (ref "P5") (pin "3") (pinfunction "3_3") (pintype "passive"))
      (node (ref "R20") (pin "1") (pinfunction "1_1") (pintype "passive"))
    )
    (net (code "72") (name "/PWM3") (class "Default")
      (node (ref "P6") (pin "3") (pinfunction "3_3") (pintype "passive"))
      (node (ref "R24") (pin "1") (pinfunction "1_1") (pintype "passive"))
    )
    (net (code "73") (name "/PWM4") (class "Default")
      (node (ref "P7") (pin "3") (pinfunction "3_3") (pintype "passive"))
      (node (ref "R26") (pin "1") (pinfunction "1_1") (pintype "passive"))
    )
    (net (code "74") (name "/PWM5") (class "Default")
      (node (ref "P9") (pin "3") (pinfunction "3_3") (pintype "passive"))
      (node (ref "R28") (pin "1") (pinfunction "1_1") (pintype "passive"))
    )
    (net (code "75") (name "/PWM6") (class "Default")
      (node (ref "P10") (pin "3") (pinfunction "3_3") (pintype "passive"))
      (node (ref "R30") (pin "1") (pinfunction "1_1") (pintype "passive"))
    )
    (net (code "76") (name "/PWM7") (class "Default")
      (node (ref "P11") (pin "3") (pinfunction "3_3") (pintype "passive"))
      (node (ref "R32") (pin "1") (pinfunction "1_1") (pintype "passive"))
    )
    (net (code "77") (name "/PWM8") (class "Default")
      (node (ref "P8") (pin "3") (pinfunction "3_3") (pintype "passive"))
      (node (ref "R34") (pin "1") (pinfunction "1_1") (pintype "passive"))
    )
    (net (code "78") (name "/PWM9") (class "Default")
      (node (ref "P13") (pin "3") (pinfunction "3_3") (pintype "passive"))
      (node (ref "R36") (pin "1") (pinfunction "1_1") (pintype "passive"))
    )
    (net (code "79") (name "/PWM10") (class "Default")
      (node (ref "P14") (pin "3") (pinfunction "3_3") (pintype "passive"))
      (node (ref "R35") (pin "1") (pinfunction "1_1") (pintype "passive"))
    )
    (net (code "80") (name "/PWM11") (class "Default")
      (node (ref "P15") (pin "3") (pinfunction "3_3") (pintype "passive"))
      (node (ref "R33") (pin "1") (pinfunction "1_1") (pintype "passive"))
    )
    (net (code "81") (name "/PWM12") (class "Default")
      (node (ref "P16") (pin "3") (pinfunction "3_3") (pintype "passive"))
      (node (ref "R31") (pin "1") (pinfunction "1_1") (pintype "passive"))
    )
    (net (code "82") (name "/PWM13") (class "Default")
      (node (ref "P17") (pin "3") (pinfunction "3_3") (pintype "passive"))
      (node (ref "R29") (pin "1") (pinfunction "1_1") (pintype "passive"))
    )
    (net (code "83") (name "/PWM14") (class "Default")
      (node (ref "P18") (pin "3") (pinfunction "3_3") (pintype "passive"))
      (node (ref "R27") (pin "1") (pinfunction "1_1") (pintype "passive"))
    )
    (net (code "84") (name "/PWM15") (class "Default")
      (node (ref "P19") (pin "3") (pinfunction "3_3") (pintype "passive"))
      (node (ref "R25") (pin "1") (pinfunction "1_1") (pintype "passive"))
    )
    (net (code "85") (name "/PWM16") (class "Default")
      (node (ref "P20") (pin "3") (pinfunction "3_3") (pintype "passive"))
      (node (ref "R21") (pin "1") (pinfunction "1_1") (pintype "passive"))
    )
    (net (code "86") (name "/RESET") (class "Default")
      (node (ref "C60") (pin "2") (pinfunction "2_2") (pintype "passive"))
      (node (ref "K1") (pin "2") (pinfunction "2_2") (pintype "passive"))
      (node (ref "P31") (pin "4") (pinfunction "4_4") (pintype "passive"))
      (node (ref "R65") (pin "2") (pinfunction "2_2") (pintype "passive"))
      (node (ref "U1") (pin "7") (pinfunction "NRST_7") (pintype "passive"))
    )
    (net (code "87") (name "/RST1") (class "Default")
      (node (ref "U5") (pin "12") (pinfunction "~{RESET}_12") (pintype "passive"))
    )
    (net (code "88") (name "/RST2") (class "Default")
      (node (ref "U7") (pin "12") (pinfunction "~{RESET}_12") (pintype "passive"))
    )
    (net (code "89") (name "/S1") (class "Default")
      (node (ref "R23") (pin "1") (pinfunction "1_1") (pintype "passive"))
      (node (ref "R46") (pin "1") (pinfunction "1_1") (pintype "passive"))
      (node (ref "U5") (pin "23") (pinfunction "SENSE1_23") (pintype "passive"))
      (node (ref "U7") (pin "23") (pinfunction "SENSE1_23") (pintype "passive"))
    )
    (net (code "90") (name "/S2") (class "Default")
      (node (ref "R22") (pin "1") (pinfunction "1_1") (pintype "passive"))
      (node (ref "R45") (pin "1") (pinfunction "1_1") (pintype "passive"))
      (node (ref "U5") (pin "27") (pinfunction "SENSE2_27") (pintype "passive"))
      (node (ref "U7") (pin "27") (pinfunction "SENSE2_27") (pintype "passive"))
    )
    (net (code "91") (name "/SLP") (class "Default")
      (node (ref "R38") (pin "1") (pinfunction "1_1") (pintype "passive"))
      (node (ref "R6") (pin "1") (pinfunction "1_1") (pintype "passive"))
      (node (ref "U5") (pin "14") (pinfunction "~{SLEEP}_14") (pintype "passive"))
      (node (ref "U7") (pin "14") (pinfunction "~{SLEEP}_14") (pintype "passive"))
    )
    (net (code "92") (name "/STEP1") (class "Default")
      (node (ref "U5") (pin "16") (pinfunction "STEP_16") (pintype "passive"))
    )
    (net (code "93") (name "/STEP2") (class "Default")
      (node (ref "U7") (pin "16") (pinfunction "STEP_16") (pintype "passive"))
    )
    (net (code "94") (name "/WIFI_RXD") (class "Default")
      (node (ref "R52") (pin "2") (pinfunction "2_2") (pintype "passive"))
      (node (ref "U15") (pin "7") (pinfunction "RXD_7") (pintype "passive"))
    )
    (net (code "95") (name "/WIFI_TXD") (class "Default")
      (node (ref "R55") (pin "2") (pinfunction "2_2") (pintype "passive"))
      (node (ref "U15") (pin "8") (pinfunction "TXD_8") (pintype "passive"))
    )
    (net (code "96") (name "/XCL") (class "Default")
      (node (ref "U2") (pin "7") (pinfunction "AUX_CL_7") (pintype "passive"))
    )
    (net (code "97") (name "/XDA") (class "Default")
      (node (ref "U2") (pin "6") (pinfunction "AUX_DA_6") (pintype "passive"))
    )
    (net (code "98") (name "/nCS") (class "Default")
      (node (ref "R47") (pin "1") (pinfunction "1_1") (pintype "passive"))
      (node (ref "U8") (pin "22") (pinfunction "nCS_22") (pintype "passive"))
    )
    (net (code "99") (name "3V3") (class "Default")
      (node (ref "C16") (pin "1") (pinfunction "1_1") (pintype "passive"))
      (node (ref "C17") (pin "1") (pinfunction "1_1") (pintype "passive"))
      (node (ref "C2") (pin "2") (pinfunction "2_2") (pintype "passive"))
      (node (ref "C52") (pin "1") (pinfunction "1_1") (pintype "passive"))
      (node (ref "C53") (pin "1") (pinfunction "1_1") (pintype "passive"))
      (node (ref "C54") (pin "1") (pinfunction "1_1") (pintype "passive"))
      (node (ref "C55") (pin "1") (pinfunction "1_1") (pintype "passive"))
      (node (ref "C56") (pin "1") (pinfunction "1_1") (pintype "passive"))
      (node (ref "C6") (pin "1") (pinfunction "1_1") (pintype "passive"))
      (node (ref "C60") (pin "1") (pinfunction "1_1") (pintype "passive"))
      (node (ref "C7") (pin "1") (pinfunction "1_1") (pintype "passive"))
      (node (ref "K1") (pin "1") (pinfunction "1_1") (pintype "passive"))
      (node (ref "P30") (pin "1") (pinfunction "3.3V_1") (pintype "passive"))
      (node (ref "R1") (pin "2") (pinfunction "2_2") (pintype "passive"))
      (node (ref "R10") (pin "1") (pinfunction "1_1") (pintype "passive"))
      (node (ref "R12") (pin "1") (pinfunction "1_1") (pintype "passive"))
      (node (ref "R13") (pin "1") (pinfunction "1_1") (pintype "passive"))
      (node (ref "R14") (pin "1") (pinfunction "1_1") (pintype "passive"))
      (node (ref "R15") (pin "1") (pinfunction "1_1") (pintype "passive"))
      (node (ref "R16") (pin "1") (pinfunction "1_1") (pintype "passive"))
      (node (ref "R17") (pin "1") (pinfunction "1_1") (pintype "passive"))
      (node (ref "R2") (pin "2") (pinfunction "2_2") (pintype "passive"))
      (node (ref "R37") (pin "2") (pinfunction "2_2") (pintype "passive"))
      (node (ref "R38") (pin "2") (pinfunction "2_2") (pintype "passive"))
      (node (ref "R43") (pin "1") (pinfunction "1_1") (pintype "passive"))
      (node (ref "R47") (pin "2") (pinfunction "2_2") (pintype "passive"))
      (node (ref "R49") (pin "1") (pinfunction "1_1") (pintype "passive"))
      (node (ref "R5") (pin "2") (pinfunction "2_2") (pintype "passive"))
      (node (ref "R52") (pin "1") (pinfunction "1_1") (pintype "passive"))
      (node (ref "R53") (pin "2") (pinfunction "2_2") (pintype "passive"))
      (node (ref "R54") (pin "2") (pinfunction "2_2") (pintype "passive"))
      (node (ref "R55") (pin "1") (pinfunction "1_1") (pintype "passive"))
      (node (ref "R6") (pin "2") (pinfunction "2_2") (pintype "passive"))
      (node (ref "R62") (pin "1") (pinfunction "1_1") (pintype "passive"))
      (node (ref "R64") (pin "1") (pinfunction "1_1") (pintype "passive"))
      (node (ref "U1") (pin "13") (pinfunction "VDDA_13") (pintype "passive"))
      (node (ref "U1") (pin "19") (pinfunction "VDD_19") (pintype "passive"))
      (node (ref "U1") (pin "32") (pinfunction "VDD_32") (pintype "passive"))
      (node (ref "U1") (pin "48") (pinfunction "VDD_48") (pintype "passive"))
      (node (ref "U1") (pin "64") (pinfunction "VDD_64") (pintype "passive"))
      (node (ref "U15") (pin "16") (pinfunction "VCC_16") (pintype "passive"))
      (node (ref "U2") (pin "13") (pinfunction "VDD_13") (pintype "passive"))
      (node (ref "U2") (pin "8") (pinfunction "VLOGIC_8") (pintype "passive"))
      (node (ref "U4") (pin "2") (pinfunction "Vout_2") (pintype "passive"))
      (node (ref "U5") (pin "15") (pinfunction "VDD_15") (pintype "passive"))
      (node (ref "U7") (pin "15") (pinfunction "VDD_15") (pintype "passive"))
      (node (ref "U8") (pin "1") (pinfunction "RESV_1") (pintype "passive"))
      (node (ref "U8") (pin "13") (pinfunction "VDD_13") (pintype "passive"))
      (node (ref "U8") (pin "8") (pinfunction "VDDIO_8") (pintype "passive"))
    )
    (net (code "100") (name "5V") (class "Default")
      (node (ref "C19") (pin "1") (pinfunction "1_1") (pintype "passive"))
      (node (ref "C5") (pin "1") (pinfunction "1_1") (pintype "passive"))
      (node (ref "L1") (pin "2") (pinfunction "2_2") (pintype "passive"))
      (node (ref "P1") (pin "2") (pinfunction "5V_2") (pintype "passive"))
      (node (ref "P10") (pin "2") (pinfunction "2_2") (pintype "passive"))
      (node (ref "P11") (pin "2") (pinfunction "2_2") (pintype "passive"))
      (node (ref "P13") (pin "2") (pinfunction "2_2") (pintype "passive"))
      (node (ref "P14") (pin "2") (pinfunction "2_2") (pintype "passive"))
      (node (ref "P15") (pin "2") (pinfunction "2_2") (pintype "passive"))
      (node (ref "P16") (pin "2") (pinfunction "2_2") (pintype "passive"))
      (node (ref "P17") (pin "2") (pinfunction "2_2") (pintype "passive"))
      (node (ref "P18") (pin "2") (pinfunction "2_2") (pintype "passive"))
      (node (ref "P19") (pin "2") (pinfunction "2_2") (pintype "passive"))
      (node (ref "P2") (pin "2") (pinfunction "5V_2") (pintype "passive"))
      (node (ref "P20") (pin "2") (pinfunction "2_2") (pintype "passive"))
      (node (ref "P4") (pin "2") (pinfunction "2_2") (pintype "passive"))
      (node (ref "P5") (pin "2") (pinfunction "2_2") (pintype "passive"))
      (node (ref "P6") (pin "2") (pinfunction "2_2") (pintype "passive"))
      (node (ref "P7") (pin "2") (pinfunction "2_2") (pintype "passive"))
      (node (ref "P8") (pin "2") (pinfunction "2_2") (pintype "passive"))
      (node (ref "P9") (pin "2") (pinfunction "2_2") (pintype "passive"))
      (node (ref "U10") (pin "1") (pinfunction "VCC_1") (pintype "passive"))
      (node (ref "U11") (pin "1") (pinfunction "VCC_1") (pintype "passive"))
      (node (ref "U12") (pin "1") (pinfunction "VCC_1") (pintype "passive"))
      (node (ref "U13") (pin "1") (pinfunction "VCC_1") (pintype "passive"))
      (node (ref "U14") (pin "7") (pinfunction "VCC_7") (pintype "passive"))
      (node (ref "U19") (pin "2") (pinfunction "OUTPUT_2") (pintype "passive"))
      (node (ref "U3") (pin "19") (pinfunction "STBY_19") (pintype "passive"))
      (node (ref "U3") (pin "20") (pinfunction "VCC_20") (pintype "passive"))
      (node (ref "U4") (pin "3") (pinfunction "Vin_3") (pintype "passive"))
      (node (ref "U6") (pin "28") (pinfunction "VDD_28") (pintype "passive"))
      (node (ref "U9") (pin "1") (pinfunction "VCC_1") (pintype "passive"))
    )
    (net (code "101") (name "12V") (class "Default")
      (node (ref "C1") (pin "2") (pinfunction "2_2") (pintype "passive"))
      (node (ref "C14") (pin "1") (pinfunction "1_1") (pintype "passive"))
      (node (ref "C15") (pin "2") (pinfunction "2_2") (pintype "passive"))
      (node (ref "R3") (pin "2") (pinfunction "2_2") (pintype "passive"))
      (node (ref "R58") (pin "2") (pinfunction "2_2") (pintype "passive"))
      (node (ref "SW1") (pin "2") (pinfunction "2_2") (pintype "passive"))
      (node (ref "U19") (pin "1") (pinfunction "VIN_1") (pintype "passive"))
      (node (ref "U3") (pin "13") (pinfunction "VM2_13") (pintype "passive"))
      (node (ref "U3") (pin "14") (pinfunction "VM3_14") (pintype "passive"))
      (node (ref "U3") (pin "24") (pinfunction "VM1_24") (pintype "passive"))
    )
    (net (code "102") (name "GND") (class "Default")
      (node (ref "C1") (pin "1") (pinfunction "1_1") (pintype "passive"))
      (node (ref "C10") (pin "2") (pinfunction "2_2") (pintype "passive"))
      (node (ref "C13") (pin "2") (pinfunction "2_2") (pintype "passive"))
      (node (ref "C14") (pin "2") (pinfunction "2_2") (pintype "passive"))
      (node (ref "C15") (pin "1") (pinfunction "1_1") (pintype "passive"))
      (node (ref "C16") (pin "2") (pinfunction "2_2") (pintype "passive"))
      (node (ref "C17") (pin "2") (pinfunction "2_2") (pintype "passive"))
      (node (ref "C18") (pin "2") (pinfunction "2_2") (pintype "passive"))
      (node (ref "C19") (pin "2") (pinfunction "2_2") (pintype "passive"))
      (node (ref "C2") (pin "1") (pinfunction "1_1") (pintype "passive"))
      (node (ref "C3") (pin "2") (pinfunction "2_2") (pintype "passive"))
      (node (ref "C4") (pin "2") (pinfunction "2_2") (pintype "passive"))
      (node (ref "C40") (pin "2") (pinfunction "2_2") (pintype "passive"))
      (node (ref "C5") (pin "2") (pinfunction "2_2") (pintype "passive"))
      (node (ref "C52") (pin "2") (pinfunction "2_2") (pintype "passive"))
      (node (ref "C53") (pin "2") (pinfunction "2_2") (pintype "passive"))
      (node (ref "C54") (pin "2") (pinfunction "2_2") (pintype "passive"))
      (node (ref "C55") (pin "2") (pinfunction "2_2") (pintype "passive"))
      (node (ref "C56") (pin "2") (pinfunction "2_2") (pintype "passive"))
      (node (ref "C58") (pin "1") (pinfunction "1_1") (pintype "passive"))
      (node (ref "C59") (pin "1") (pinfunction "1_1") (pintype "passive"))
      (node (ref "C6") (pin "2") (pinfunction "2_2") (pintype "passive"))
      (node (ref "C7") (pin "2") (pinfunction "2_2") (pintype "passive"))
      (node (ref "D1") (pin "1") (pinfunction "1_1") (pintype "passive"))
      (node (ref "D4") (pin "2") (pinfunction "2_2") (pintype "passive"))
      (node (ref "D5") (pin "2") (pinfunction "2_2") (pintype "passive"))
      (node (ref "P1") (pin "5") (pinfunction "GND_5") (pintype "passive"))
      (node (ref "P10") (pin "1") (pinfunction "1_1") (pintype "passive"))
      (node (ref "P11") (pin "1") (pinfunction "1_1") (pintype "passive"))
      (node (ref "P13") (pin "1") (pinfunction "1_1") (pintype "passive"))
      (node (ref "P14") (pin "1") (pinfunction "1_1") (pintype "passive"))
      (node (ref "P15") (pin "1") (pinfunction "1_1") (pintype "passive"))
      (node (ref "P16") (pin "1") (pinfunction "1_1") (pintype "passive"))
      (node (ref "P17") (pin "1") (pinfunction "1_1") (pintype "passive"))
      (node (ref "P18") (pin "1") (pinfunction "1_1") (pintype "passive"))
      (node (ref "P19") (pin "1") (pinfunction "1_1") (pintype "passive"))
      (node (ref "P2") (pin "5") (pinfunction "GND_5") (pintype "passive"))
      (node (ref "P20") (pin "1") (pinfunction "1_1") (pintype "passive"))
      (node (ref "P26") (pin "2") (pinfunction "2_2") (pintype "passive"))
      (node (ref "P29") (pin "3") (pinfunction "3_3") (pintype "passive"))
      (node (ref "P30") (pin "4") (pinfunction "GND_4") (pintype "passive"))
      (node (ref "P4") (pin "1") (pinfunction "1_1") (pintype "passive"))
      (node (ref "P5") (pin "1") (pinfunction "1_1") (pintype "passive"))
      (node (ref "P6") (pin "1") (pinfunction "1_1") (pintype "passive"))
      (node (ref "P7") (pin "1") (pinfunction "1_1") (pintype "passive"))
      (node (ref "P8") (pin "1") (pinfunction "1_1") (pintype "passive"))
      (node (ref "P9") (pin "1") (pinfunction "1_1") (pintype "passive"))
      (node (ref "R22") (pin "2") (pinfunction "2_2") (pintype "passive"))
      (node (ref "R23") (pin "2") (pinfunction "2_2") (pintype "passive"))
      (node (ref "R39") (pin "2") (pinfunction "2_2") (pintype "passive"))
      (node (ref "R4") (pin "1") (pinfunction "1_1") (pintype "passive"))
      (node (ref "R45") (pin "2") (pinfunction "2_2") (pintype "passive"))
      (node (ref "R46") (pin "2") (pinfunction "2_2") (pintype "passive"))
      (node (ref "R48") (pin "1") (pinfunction "1_1") (pintype "passive"))
      (node (ref "R50") (pin "1") (pinfunction "1_1") (pintype "passive"))
      (node (ref "R51") (pin "1") (pinfunction "1_1") (pintype "passive"))
      (node (ref "R61") (pin "2") (pinfunction "2_2") (pintype "passive"))
      (node (ref "R63") (pin "1") (pinfunction "1_1") (pintype "passive"))
      (node (ref "R65") (pin "1") (pinfunction "1_1") (pintype "passive"))
      (node (ref "R7") (pin "2") (pinfunction "2_2") (pintype "passive"))
      (node (ref "U1") (pin "12") (pinfunction "VSSA_12") (pintype "passive"))
      (node (ref "U1") (pin "18") (pinfunction "VSS_18") (pintype "passive"))
      (node (ref "U1") (pin "31") (pinfunction "VSS_31") (pintype "passive"))
      (node (ref "U1") (pin "47") (pinfunction "VSS_47") (pintype "passive"))
      (node (ref "U1") (pin "63") (pinfunction "VSS_63") (pintype "passive"))
      (node (ref "U10") (pin "4") (pinfunction "GND_4") (pintype "passive"))
      (node (ref "U11") (pin "4") (pinfunction "GND_4") (pintype "passive"))
      (node (ref "U12") (pin "4") (pinfunction "GND_4") (pintype "passive"))
      (node (ref "U13") (pin "5") (pinfunction "GND_5") (pintype "passive"))
      (node (ref "U14") (pin "3") (pinfunction "GND_3") (pintype "passive"))
      (node (ref "U15") (pin "1") (pinfunction "GND_1") (pintype "open_emitter"))
      (node (ref "U19") (pin "3") (pinfunction "GND_3") (pintype "passive"))
      (node (ref "U19") (pin "5") (pinfunction "ON/OFF_5") (pintype "passive"))
      (node (ref "U2") (pin "1") (pinfunction "CLKIN_1") (pintype "passive"))
      (node (ref "U2") (pin "11") (pinfunction "FSYNC_11") (pintype "passive"))
      (node (ref "U2") (pin "18") (pinfunction "GND_18") (pintype "passive"))
      (node (ref "U3") (pin "18") (pinfunction "GND_18") (pintype "passive"))
      (node (ref "U4") (pin "1") (pinfunction "GND_1") (pintype "passive"))
      (node (ref "U5") (pin "18") (pinfunction "GND_18") (pintype "passive"))
      (node (ref "U5") (pin "29") (pinfunction "PAD_29") (pintype "passive"))
      (node (ref "U5") (pin "3") (pinfunction "GND_3") (pintype "passive"))
      (node (ref "U6") (pin "14") (pinfunction "VSS_14") (pintype "passive"))
      (node (ref "U7") (pin "18") (pinfunction "GND_18") (pintype "passive"))
      (node (ref "U7") (pin "29") (pinfunction "PAD_29") (pintype "passive"))
      (node (ref "U7") (pin "3") (pinfunction "GND_3") (pintype "passive"))
      (node (ref "U8") (pin "18") (pinfunction "GND_18") (pintype "passive"))
      (node (ref "U8") (pin "20") (pinfunction "RESV_20") (pintype "passive"))
      (node (ref "U9") (pin "4") (pinfunction "GND_4") (pintype "passive"))
    )
    (net (code "103") (name "Net-(C3-Pad1)") (class "Default")
      (node (ref "C3") (pin "1") (pinfunction "1_1") (pintype "passive"))
      (node (ref "U2") (pin "19") (pinfunction "RESV_19") (pintype "passive"))
    )
    (net (code "104") (name "Net-(D4-Pad1)") (class "Default")
      (node (ref "D4") (pin "1") (pinfunction "1_1") (pintype "passive"))
      (node (ref "R56") (pin "2") (pinfunction "2_2") (pintype "passive"))
    )
    (net (code "105") (name "Net-(D5-Pad1)") (class "Default")
      (node (ref "D5") (pin "1") (pinfunction "1_1") (pintype "passive"))
      (node (ref "R57") (pin "2") (pinfunction "2_2") (pintype "passive"))
    )
    (net (code "106") (name "Net-(P26-Pad1)") (class "Default")
      (node (ref "P26") (pin "1") (pinfunction "1_1") (pintype "passive"))
      (node (ref "SW1") (pin "1") (pinfunction "1_1") (pintype "passive"))
    )
    (net (code "107") (name "Net-(R15-Pad2)") (class "Default")
      (node (ref "R15") (pin "2") (pinfunction "2_2") (pintype "passive"))
      (node (ref "R19") (pin "1") (pinfunction "1_1") (pintype "passive"))
    )
    (net (code "108") (name "Net-(R43-Pad2)") (class "Default")
      (node (ref "R43") (pin "2") (pinfunction "2_2") (pintype "passive"))
      (node (ref "R44") (pin "1") (pinfunction "1_1") (pintype "passive"))
    )
    (net (code "109") (name "Net-(U1-BOOT0)") (class "Default")
      (node (ref "R61") (pin "1") (pinfunction "1_1") (pintype "passive"))
      (node (ref "U1") (pin "60") (pinfunction "BOOT0_60") (pintype "passive"))
    )
    (net (code "110") (name "Net-(U2-REGOUT)") (class "Default")
      (node (ref "C4") (pin "1") (pinfunction "1_1") (pintype "passive"))
      (node (ref "U2") (pin "10") (pinfunction "REGOUT_10") (pintype "passive"))
    )
    (net (code "111") (name "Net-(U5-CP1)") (class "Default")
      (node (ref "C8") (pin "2") (pinfunction "2_2") (pintype "passive"))
      (node (ref "U5") (pin "4") (pinfunction "CP1_4") (pintype "passive"))
    )
    (net (code "112") (name "Net-(U5-CP2)") (class "Default")
      (node (ref "C8") (pin "1") (pinfunction "1_1") (pintype "passive"))
      (node (ref "U5") (pin "5") (pinfunction "CP2_5") (pintype "passive"))
    )
    (net (code "113") (name "Net-(U5-MS1)") (class "Default")
      (node (ref "R8") (pin "1") (pinfunction "1_1") (pintype "passive"))
      (node (ref "U5") (pin "9") (pinfunction "MS1_9") (pintype "passive"))
    )
    (net (code "114") (name "Net-(U5-MS2)") (class "Default")
      (node (ref "R9") (pin "1") (pinfunction "1_1") (pintype "passive"))
      (node (ref "U5") (pin "10") (pinfunction "MS2_10") (pintype "passive"))
    )
    (net (code "115") (name "Net-(U5-MS3)") (class "Default")
      (node (ref "R11") (pin "1") (pinfunction "1_1") (pintype "passive"))
      (node (ref "U5") (pin "11") (pinfunction "MS3_11") (pintype "passive"))
    )
    (net (code "116") (name "Net-(U5-REF)") (class "Default")
      (node (ref "R19") (pin "2") (pinfunction "2_2") (pintype "passive"))
      (node (ref "U5") (pin "17") (pinfunction "REF_17") (pintype "passive"))
    )
    (net (code "117") (name "Net-(U5-ROSC)") (class "Default")
      (node (ref "R5") (pin "1") (pinfunction "1_1") (pintype "passive"))
      (node (ref "R7") (pin "1") (pinfunction "1_1") (pintype "passive"))
      (node (ref "U5") (pin "13") (pinfunction "ROSC_13") (pintype "passive"))
    )
    (net (code "118") (name "Net-(U5-VCP)") (class "Default")
      (node (ref "C9") (pin "2") (pinfunction "2_2") (pintype "passive"))
      (node (ref "U5") (pin "6") (pinfunction "VCP_6") (pintype "passive"))
    )
    (net (code "119") (name "Net-(U5-VREG)") (class "Default")
      (node (ref "C10") (pin "1") (pinfunction "1_1") (pintype "passive"))
      (node (ref "U5") (pin "8") (pinfunction "VREG_8") (pintype "passive"))
    )
    (net (code "120") (name "Net-(U6-A0)") (class "Default")
      (node (ref "R10") (pin "2") (pinfunction "2_2") (pintype "passive"))
      (node (ref "U6") (pin "1") (pinfunction "A0_1") (pintype "passive"))
    )
    (net (code "121") (name "Net-(U6-A1)") (class "Default")
      (node (ref "R12") (pin "2") (pinfunction "2_2") (pintype "passive"))
      (node (ref "U6") (pin "2") (pinfunction "A1_2") (pintype "passive"))
    )
    (net (code "122") (name "Net-(U6-A2)") (class "Default")
      (node (ref "R13") (pin "2") (pinfunction "2_2") (pintype "passive"))
      (node (ref "U6") (pin "3") (pinfunction "A2_3") (pintype "passive"))
    )
    (net (code "123") (name "Net-(U6-A3)") (class "Default")
      (node (ref "R14") (pin "2") (pinfunction "2_2") (pintype "passive"))
      (node (ref "U6") (pin "4") (pinfunction "A3_4") (pintype "passive"))
    )
    (net (code "124") (name "Net-(U6-A4)") (class "Default")
      (node (ref "R16") (pin "2") (pinfunction "2_2") (pintype "passive"))
      (node (ref "U6") (pin "5") (pinfunction "A4_5") (pintype "passive"))
    )
    (net (code "125") (name "Net-(U6-A5)") (class "Default")
      (node (ref "R17") (pin "2") (pinfunction "2_2") (pintype "passive"))
      (node (ref "U6") (pin "24") (pinfunction "A5_24") (pintype "passive"))
    )
    (net (code "126") (name "Net-(U6-LED0)") (class "Default")
      (node (ref "R18") (pin "2") (pinfunction "2_2") (pintype "passive"))
      (node (ref "U6") (pin "6") (pinfunction "LED0_6") (pintype "passive"))
    )
    (net (code "127") (name "Net-(U6-LED1)") (class "Default")
      (node (ref "R20") (pin "2") (pinfunction "2_2") (pintype "passive"))
      (node (ref "U6") (pin "7") (pinfunction "LED1_7") (pintype "passive"))
    )
    (net (code "128") (name "Net-(U6-LED2)") (class "Default")
      (node (ref "R24") (pin "2") (pinfunction "2_2") (pintype "passive"))
      (node (ref "U6") (pin "8") (pinfunction "LED2_8") (pintype "passive"))
    )
    (net (code "129") (name "Net-(U6-LED3)") (class "Default")
      (node (ref "R26") (pin "2") (pinfunction "2_2") (pintype "passive"))
      (node (ref "U6") (pin "9") (pinfunction "LED3_9") (pintype "passive"))
    )
    (net (code "130") (name "Net-(U6-LED4)") (class "Default")
      (node (ref "R28") (pin "2") (pinfunction "2_2") (pintype "passive"))
      (node (ref "U6") (pin "10") (pinfunction "LED4_10") (pintype "passive"))
    )
    (net (code "131") (name "Net-(U6-LED5)") (class "Default")
      (node (ref "R30") (pin "2") (pinfunction "2_2") (pintype "passive"))
      (node (ref "U6") (pin "11") (pinfunction "LED5_11") (pintype "passive"))
    )
    (net (code "132") (name "Net-(U6-LED6)") (class "Default")
      (node (ref "R32") (pin "2") (pinfunction "2_2") (pintype "passive"))
      (node (ref "U6") (pin "12") (pinfunction "LED6_12") (pintype "passive"))
    )
    (net (code "133") (name "Net-(U6-LED7)") (class "Default")
      (node (ref "R34") (pin "2") (pinfunction "2_2") (pintype "passive"))
      (node (ref "U6") (pin "13") (pinfunction "LED7_13") (pintype "passive"))
    )
    (net (code "134") (name "Net-(U6-LED8)") (class "Default")
      (node (ref "R36") (pin "2") (pinfunction "2_2") (pintype "passive"))
      (node (ref "U6") (pin "15") (pinfunction "LED8_15") (pintype "passive"))
    )
    (net (code "135") (name "Net-(U6-LED9)") (class "Default")
      (node (ref "R35") (pin "2") (pinfunction "2_2") (pintype "passive"))
      (node (ref "U6") (pin "16") (pinfunction "LED9_16") (pintype "passive"))
    )
    (net (code "136") (name "Net-(U6-LED10)") (class "Default")
      (node (ref "R33") (pin "2") (pinfunction "2_2") (pintype "passive"))
      (node (ref "U6") (pin "17") (pinfunction "LED10_17") (pintype "passive"))
    )
    (net (code "137") (name "Net-(U6-LED11)") (class "Default")
      (node (ref "R31") (pin "2") (pinfunction "2_2") (pintype "passive"))
      (node (ref "U6") (pin "18") (pinfunction "LED11_18") (pintype "passive"))
    )
    (net (code "138") (name "Net-(U6-LED12)") (class "Default")
      (node (ref "R29") (pin "2") (pinfunction "2_2") (pintype "passive"))
      (node (ref "U6") (pin "19") (pinfunction "LED12_19") (pintype "passive"))
    )
    (net (code "139") (name "Net-(U6-LED13)") (class "Default")
      (node (ref "R27") (pin "2") (pinfunction "2_2") (pintype "passive"))
      (node (ref "U6") (pin "20") (pinfunction "LED13_20") (pintype "passive"))
    )
    (net (code "140") (name "Net-(U6-LED14)") (class "Default")
      (node (ref "R25") (pin "2") (pinfunction "2_2") (pintype "passive"))
      (node (ref "U6") (pin "21") (pinfunction "LED14_21") (pintype "passive"))
    )
    (net (code "141") (name "Net-(U6-LED15)") (class "Default")
      (node (ref "R21") (pin "2") (pinfunction "2_2") (pintype "passive"))
      (node (ref "U6") (pin "22") (pinfunction "LED15_22") (pintype "passive"))
    )
    (net (code "142") (name "Net-(U7-CP1)") (class "Default")
      (node (ref "C11") (pin "2") (pinfunction "2_2") (pintype "passive"))
      (node (ref "U7") (pin "4") (pinfunction "CP1_4") (pintype "passive"))
    )
    (net (code "143") (name "Net-(U7-CP2)") (class "Default")
      (node (ref "C11") (pin "1") (pinfunction "1_1") (pintype "passive"))
      (node (ref "U7") (pin "5") (pinfunction "CP2_5") (pintype "passive"))
    )
    (net (code "144") (name "Net-(U7-MS1)") (class "Default")
      (node (ref "R40") (pin "1") (pinfunction "1_1") (pintype "passive"))
      (node (ref "U7") (pin "9") (pinfunction "MS1_9") (pintype "passive"))
    )
    (net (code "145") (name "Net-(U7-MS2)") (class "Default")
      (node (ref "R41") (pin "1") (pinfunction "1_1") (pintype "passive"))
      (node (ref "U7") (pin "10") (pinfunction "MS2_10") (pintype "passive"))
    )
    (net (code "146") (name "Net-(U7-MS3)") (class "Default")
      (node (ref "R42") (pin "1") (pinfunction "1_1") (pintype "passive"))
      (node (ref "U7") (pin "11") (pinfunction "MS3_11") (pintype "passive"))
    )
    (net (code "147") (name "Net-(U7-REF)") (class "Default")
      (node (ref "R44") (pin "2") (pinfunction "2_2") (pintype "passive"))
      (node (ref "U7") (pin "17") (pinfunction "REF_17") (pintype "passive"))
    )
    (net (code "148") (name "Net-(U7-ROSC)") (class "Default")
      (node (ref "R37") (pin "1") (pinfunction "1_1") (pintype "passive"))
      (node (ref "R39") (pin "1") (pinfunction "1_1") (pintype "passive"))
      (node (ref "U7") (pin "13") (pinfunction "ROSC_13") (pintype "passive"))
    )
    (net (code "149") (name "Net-(U7-VCP)") (class "Default")
      (node (ref "C12") (pin "2") (pinfunction "2_2") (pintype "passive"))
      (node (ref "U7") (pin "6") (pinfunction "VCP_6") (pintype "passive"))
    )
    (net (code "150") (name "Net-(U7-VREG)") (class "Default")
      (node (ref "C13") (pin "1") (pinfunction "1_1") (pintype "passive"))
      (node (ref "U7") (pin "8") (pinfunction "VREG_8") (pintype "passive"))
    )
    (net (code "151") (name "Net-(U8-REGOUT)") (class "Default")
      (node (ref "C18") (pin "1") (pinfunction "1_1") (pintype "passive"))
      (node (ref "U8") (pin "10") (pinfunction "REGOUT_10") (pintype "passive"))
    )
    (net (code "152") (name "Net-(U13-D+)") (class "Default")
      (node (ref "U13") (pin "3") (pinfunction "D+_3") (pintype "passive"))
      (node (ref "U14") (pin "1") (pinfunction "UD+_1") (pintype "passive"))
    )
    (net (code "153") (name "Net-(U13-D-)") (class "Default")
      (node (ref "U13") (pin "2") (pinfunction "D-_2") (pintype "passive"))
      (node (ref "U14") (pin "2") (pinfunction "UD-_2") (pintype "passive"))
    )
    (net (code "154") (name "Net-(U14-V3)") (class "Default")
      (node (ref "C40") (pin "1") (pinfunction "1_1") (pintype "passive"))
      (node (ref "U14") (pin "10") (pinfunction "V3_10") (pintype "passive"))
    )
    (net (code "155") (name "Net-(U15-CH_PD)") (class "Default")
      (node (ref "R53") (pin "1") (pinfunction "1_1") (pintype "passive"))
      (node (ref "U15") (pin "11") (pinfunction "CH_PD_11") (pintype "passive"))
    )
    (net (code "156") (name "Net-(U15-GPIO0)") (class "Default")
      (node (ref "R49") (pin "2") (pinfunction "2_2") (pintype "passive"))
      (node (ref "U15") (pin "4") (pinfunction "GPIO0_4") (pintype "passive"))
    )
    (net (code "157") (name "Net-(U15-GPIO15)") (class "Default")
      (node (ref "R48") (pin "2") (pinfunction "2_2") (pintype "passive"))
      (node (ref "U15") (pin "2") (pinfunction "GPIO15_2") (pintype "passive"))
    )
    (net (code "158") (name "Net-(U15-RESET)") (class "Default")
      (node (ref "R54") (pin "1") (pinfunction "1_1") (pintype "passive"))
      (node (ref "U15") (pin "9") (pinfunction "RESET_9") (pintype "passive"))
    )
    (net (code "159") (name "Net-(U19-FB)") (class "Default")
      (node (ref "D1") (pin "2") (pinfunction "2_2") (pintype "passive"))
      (node (ref "L1") (pin "1") (pinfunction "1_1") (pintype "passive"))
      (node (ref "U19") (pin "4") (pinfunction "FB_4") (pintype "passive"))
    )
    (net (code "160") (name "VMM") (class "Default")
      (node (ref "C12") (pin "1") (pinfunction "1_1") (pintype "passive"))
      (node (ref "C9") (pin "1") (pinfunction "1_1") (pintype "passive"))
      (node (ref "R58") (pin "1") (pinfunction "1_1") (pintype "passive"))
      (node (ref "U5") (pin "22") (pinfunction "VBB1_22") (pintype "passive"))
      (node (ref "U5") (pin "28") (pinfunction "VBB2_28") (pintype "passive"))
      (node (ref "U7") (pin "22") (pinfunction "VBB1_22") (pintype "passive"))
      (node (ref "U7") (pin "28") (pinfunction "VBB2_28") (pintype "passive"))
    )
    (net (code "161") (name "unconnected-(SW1-Pad3)") (class "Default")
      (node (ref "SW1") (pin "3") (pinfunction "3_3") (pintype "passive"))
    )
    (net (code "162") (name "unconnected-(U1-VBAT-Pad1)") (class "Default")
      (node (ref "U1") (pin "1") (pinfunction "VBAT_1") (pintype "passive"))
    )
    (net (code "163") (name "unconnected-(U2-CPOUT-Pad20)") (class "Default")
      (node (ref "U2") (pin "20") (pinfunction "CPOUT_20") (pintype "passive+no_connect"))
    )
    (net (code "164") (name "unconnected-(U2-NC-Pad2)") (class "Default")
      (node (ref "U2") (pin "2") (pinfunction "NC_2") (pintype "passive+no_connect"))
    )
    (net (code "165") (name "unconnected-(U2-NC-Pad3)") (class "Default")
      (node (ref "U2") (pin "3") (pinfunction "NC_3") (pintype "passive+no_connect"))
    )
    (net (code "166") (name "unconnected-(U2-NC-Pad4)") (class "Default")
      (node (ref "U2") (pin "4") (pinfunction "NC_4") (pintype "passive+no_connect"))
    )
    (net (code "167") (name "unconnected-(U2-NC-Pad5)") (class "Default")
      (node (ref "U2") (pin "5") (pinfunction "NC_5") (pintype "passive+no_connect"))
    )
    (net (code "168") (name "unconnected-(U2-NC-Pad14)") (class "Default")
      (node (ref "U2") (pin "14") (pinfunction "NC_14") (pintype "passive+no_connect"))
    )
    (net (code "169") (name "unconnected-(U2-NC-Pad15)") (class "Default")
      (node (ref "U2") (pin "15") (pinfunction "NC_15") (pintype "passive+no_connect"))
    )
    (net (code "170") (name "unconnected-(U2-NC-Pad16)") (class "Default")
      (node (ref "U2") (pin "16") (pinfunction "NC_16") (pintype "passive+no_connect"))
    )
    (net (code "171") (name "unconnected-(U2-NC-Pad17)") (class "Default")
      (node (ref "U2") (pin "17") (pinfunction "NC_17") (pintype "passive+no_connect"))
    )
    (net (code "172") (name "unconnected-(U2-RESV-Pad21)") (class "Default")
      (node (ref "U2") (pin "21") (pinfunction "RESV_21") (pintype "passive+no_connect"))
    )
    (net (code "173") (name "unconnected-(U2-RESV-Pad22)") (class "Default")
      (node (ref "U2") (pin "22") (pinfunction "RESV_22") (pintype "passive+no_connect"))
    )
    (net (code "174") (name "unconnected-(U3-PGND1-Pad3)") (class "Default")
      (node (ref "U3") (pin "3") (pinfunction "PGND1_3") (pintype "passive"))
    )
    (net (code "175") (name "unconnected-(U3-PGND1-Pad4)") (class "Default")
      (node (ref "U3") (pin "4") (pinfunction "PGND1_4") (pintype "passive"))
    )
    (net (code "176") (name "unconnected-(U3-PGND2-Pad9)") (class "Default")
      (node (ref "U3") (pin "9") (pinfunction "PGND2_9") (pintype "passive"))
    )
    (net (code "177") (name "unconnected-(U3-PGND2-Pad10)") (class "Default")
      (node (ref "U3") (pin "10") (pinfunction "PGND2_10") (pintype "passive"))
    )
    (net (code "178") (name "unconnected-(U5-NC-Pad7)") (class "Default")
      (node (ref "U5") (pin "7") (pinfunction "NC_7") (pintype "passive+no_connect"))
    )
    (net (code "179") (name "unconnected-(U5-NC-Pad20)") (class "Default")
      (node (ref "U5") (pin "20") (pinfunction "NC_20") (pintype "passive+no_connect"))
    )
    (net (code "180") (name "unconnected-(U5-NC-Pad25)") (class "Default")
      (node (ref "U5") (pin "25") (pinfunction "NC_25") (pintype "passive+no_connect"))
    )
    (net (code "181") (name "unconnected-(U6-EXTCLK-Pad25)") (class "Default")
      (node (ref "U6") (pin "25") (pinfunction "EXTCLK_25") (pintype "passive+no_connect"))
    )
    (net (code "182") (name "unconnected-(U6-~{OE}-Pad23)") (class "Default")
      (node (ref "U6") (pin "23") (pinfunction "~{OE}_23") (pintype "passive"))
    )
    (net (code "183") (name "unconnected-(U7-NC-Pad7)") (class "Default")
      (node (ref "U7") (pin "7") (pinfunction "NC_7") (pintype "passive+no_connect"))
    )
    (net (code "184") (name "unconnected-(U7-NC-Pad20)") (class "Default")
      (node (ref "U7") (pin "20") (pinfunction "NC_20") (pintype "passive+no_connect"))
    )
    (net (code "185") (name "unconnected-(U7-NC-Pad25)") (class "Default")
      (node (ref "U7") (pin "25") (pinfunction "NC_25") (pintype "passive+no_connect"))
    )
    (net (code "186") (name "unconnected-(U8-NC-Pad2)") (class "Default")
      (node (ref "U8") (pin "2") (pinfunction "NC_2") (pintype "passive+no_connect"))
    )
    (net (code "187") (name "unconnected-(U8-NC-Pad3)") (class "Default")
      (node (ref "U8") (pin "3") (pinfunction "NC_3") (pintype "passive+no_connect"))
    )
    (net (code "188") (name "unconnected-(U8-NC-Pad4)") (class "Default")
      (node (ref "U8") (pin "4") (pinfunction "NC_4") (pintype "passive+no_connect"))
    )
    (net (code "189") (name "unconnected-(U8-NC-Pad5)") (class "Default")
      (node (ref "U8") (pin "5") (pinfunction "NC_5") (pintype "passive+no_connect"))
    )
    (net (code "190") (name "unconnected-(U8-NC-Pad6)") (class "Default")
      (node (ref "U8") (pin "6") (pinfunction "NC_6") (pintype "passive+no_connect"))
    )
    (net (code "191") (name "unconnected-(U8-NC-Pad14)") (class "Default")
      (node (ref "U8") (pin "14") (pinfunction "NC_14") (pintype "passive+no_connect"))
    )
    (net (code "192") (name "unconnected-(U8-NC-Pad15)") (class "Default")
      (node (ref "U8") (pin "15") (pinfunction "NC_15") (pintype "passive+no_connect"))
    )
    (net (code "193") (name "unconnected-(U8-NC-Pad16)") (class "Default")
      (node (ref "U8") (pin "16") (pinfunction "NC_16") (pintype "passive+no_connect"))
    )
    (net (code "194") (name "unconnected-(U8-NC-Pad17)") (class "Default")
      (node (ref "U8") (pin "17") (pinfunction "NC_17") (pintype "passive+no_connect"))
    )
    (net (code "195") (name "unconnected-(U8-RESV-Pad19)") (class "Default")
      (node (ref "U8") (pin "19") (pinfunction "RESV_19") (pintype "passive+no_connect"))
    )
    (net (code "196") (name "unconnected-(U13-ID-Pad4)") (class "Default")
      (node (ref "U13") (pin "4") (pinfunction "ID_4") (pintype "passive"))
    )
    (net (code "197") (name "unconnected-(U14-CTS#-Pad5)") (class "Default")
      (node (ref "U14") (pin "5") (pinfunction "CTS#_5") (pintype "passive"))
    )
    (net (code "198") (name "unconnected-(U14-RTS#-Pad4)") (class "Default")
      (node (ref "U14") (pin "4") (pinfunction "RTS#_4") (pintype "passive"))
    )
    (net (code "199") (name "unconnected-(U14-TNOW-Pad6)") (class "Default")
      (node (ref "U14") (pin "6") (pinfunction "TNOW_6") (pintype "passive+no_connect"))
    )
    (net (code "200") (name "unconnected-(U15-ADC-Pad10)") (class "Default")
      (node (ref "U15") (pin "10") (pinfunction "ADC_10") (pintype "passive"))
    )
    (net (code "201") (name "unconnected-(U15-GPIO2-Pad3)") (class "Default")
      (node (ref "U15") (pin "3") (pinfunction "GPIO2_3") (pintype "passive"))
    )
    (net (code "202") (name "unconnected-(U15-GPIO4-Pad6)") (class "Default")
      (node (ref "U15") (pin "6") (pinfunction "GPIO4_6") (pintype "passive+no_connect"))
    )
    (net (code "203") (name "unconnected-(U15-GPIO5-Pad5)") (class "Default")
      (node (ref "U15") (pin "5") (pinfunction "GPIO5_5") (pintype "passive+no_connect"))
    )
    (net (code "204") (name "unconnected-(U15-GPIO9-Pad22)") (class "Default")
      (node (ref "U15") (pin "22") (pinfunction "GPIO9_22") (pintype "passive+no_connect"))
    )
    (net (code "205") (name "unconnected-(U15-GPIO10-Pad19)") (class "Default")
      (node (ref "U15") (pin "19") (pinfunction "GPIO10_19") (pintype "passive+no_connect"))
    )
    (net (code "206") (name "unconnected-(U15-GPIO12-Pad14)") (class "Default")
      (node (ref "U15") (pin "14") (pinfunction "GPIO12_14") (pintype "passive+no_connect"))
    )
    (net (code "207") (name "unconnected-(U15-GPIO13-Pad15)") (class "Default")
      (node (ref "U15") (pin "15") (pinfunction "GPIO13_15") (pintype "passive+no_connect"))
    )
    (net (code "208") (name "unconnected-(U15-GPIO14-Pad13)") (class "Default")
      (node (ref "U15") (pin "13") (pinfunction "GPIO14_13") (pintype "passive+no_connect"))
    )
    (net (code "209") (name "unconnected-(U15-GPIO16-Pad12)") (class "Default")
      (node (ref "U15") (pin "12") (pinfunction "GPIO16_12") (pintype "passive+no_connect"))
    )
    (net (code "210") (name "unconnected-(U15-MTCK-Pad21)") (class "Default")
      (node (ref "U15") (pin "21") (pinfunction "MTCK_21") (pintype "passive+no_connect"))
    )
    (net (code "211") (name "unconnected-(U15-MTDI-Pad18)") (class "Default")
      (node (ref "U15") (pin "18") (pinfunction "MTDI_18") (pintype "passive+no_connect"))
    )
    (net (code "212") (name "unconnected-(U15-MTDO-Pad17)") (class "Default")
      (node (ref "U15") (pin "17") (pinfunction "MTDO_17") (pintype "passive+no_connect"))
    )
    (net (code "213") (name "unconnected-(U15-MTMS-Pad20)") (class "Default")
      (node (ref "U15") (pin "20") (pinfunction "MTMS_20") (pintype "passive+no_connect"))
    )
  )
)
